# Power_supply.net
KiCad netlist of a schematic drawn in EAGLE
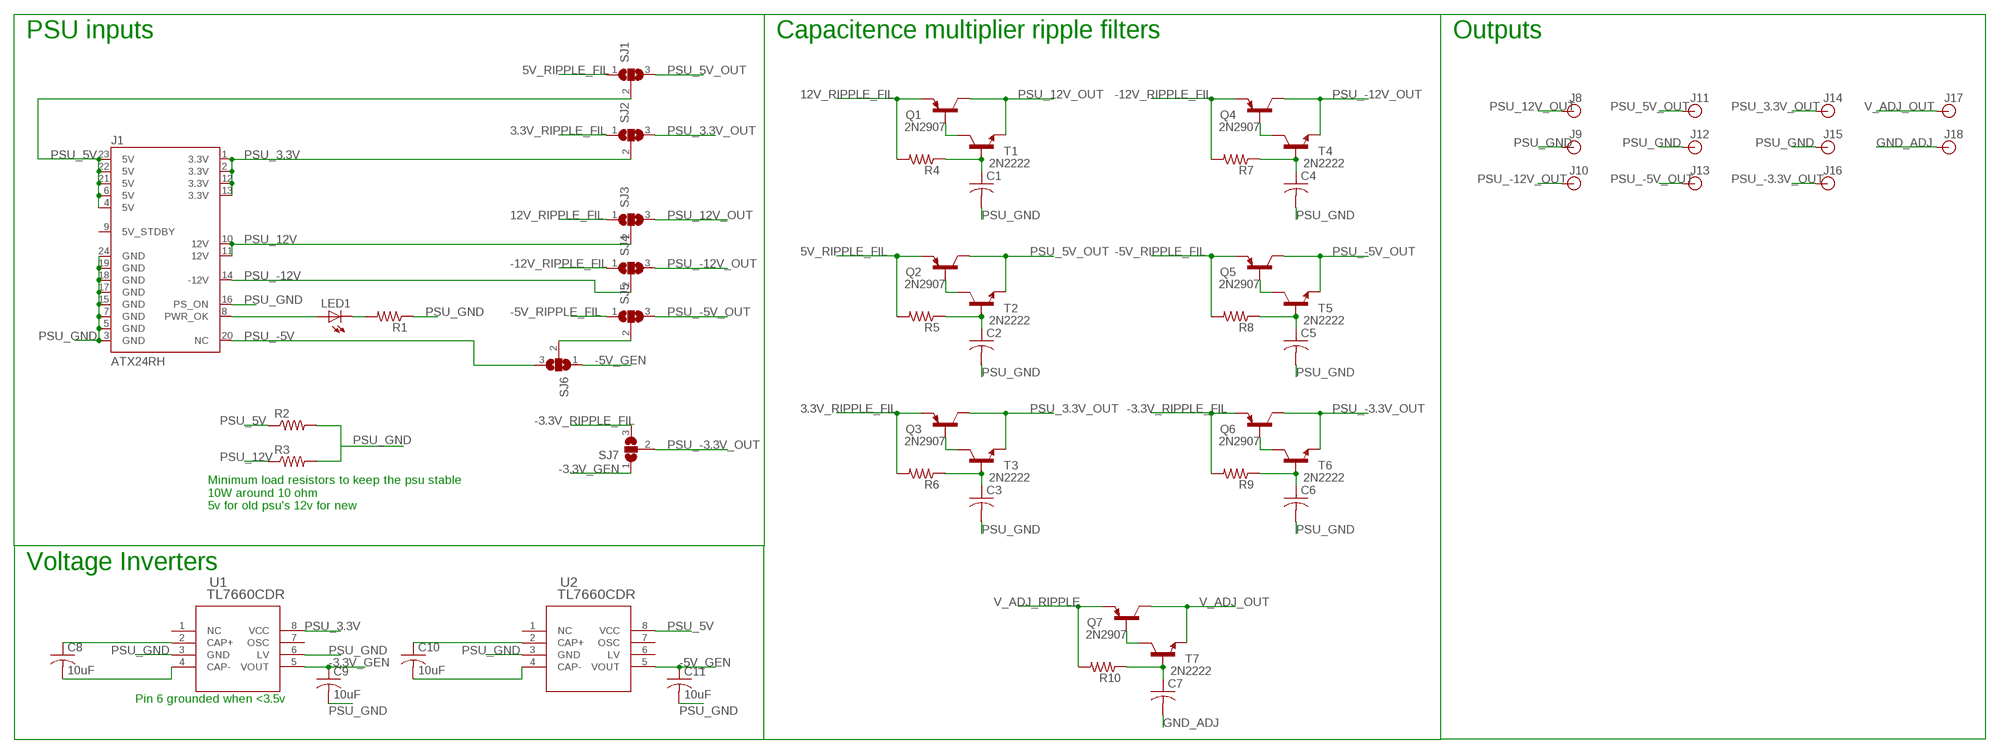
[diagram p0: schematic, sheet 1]
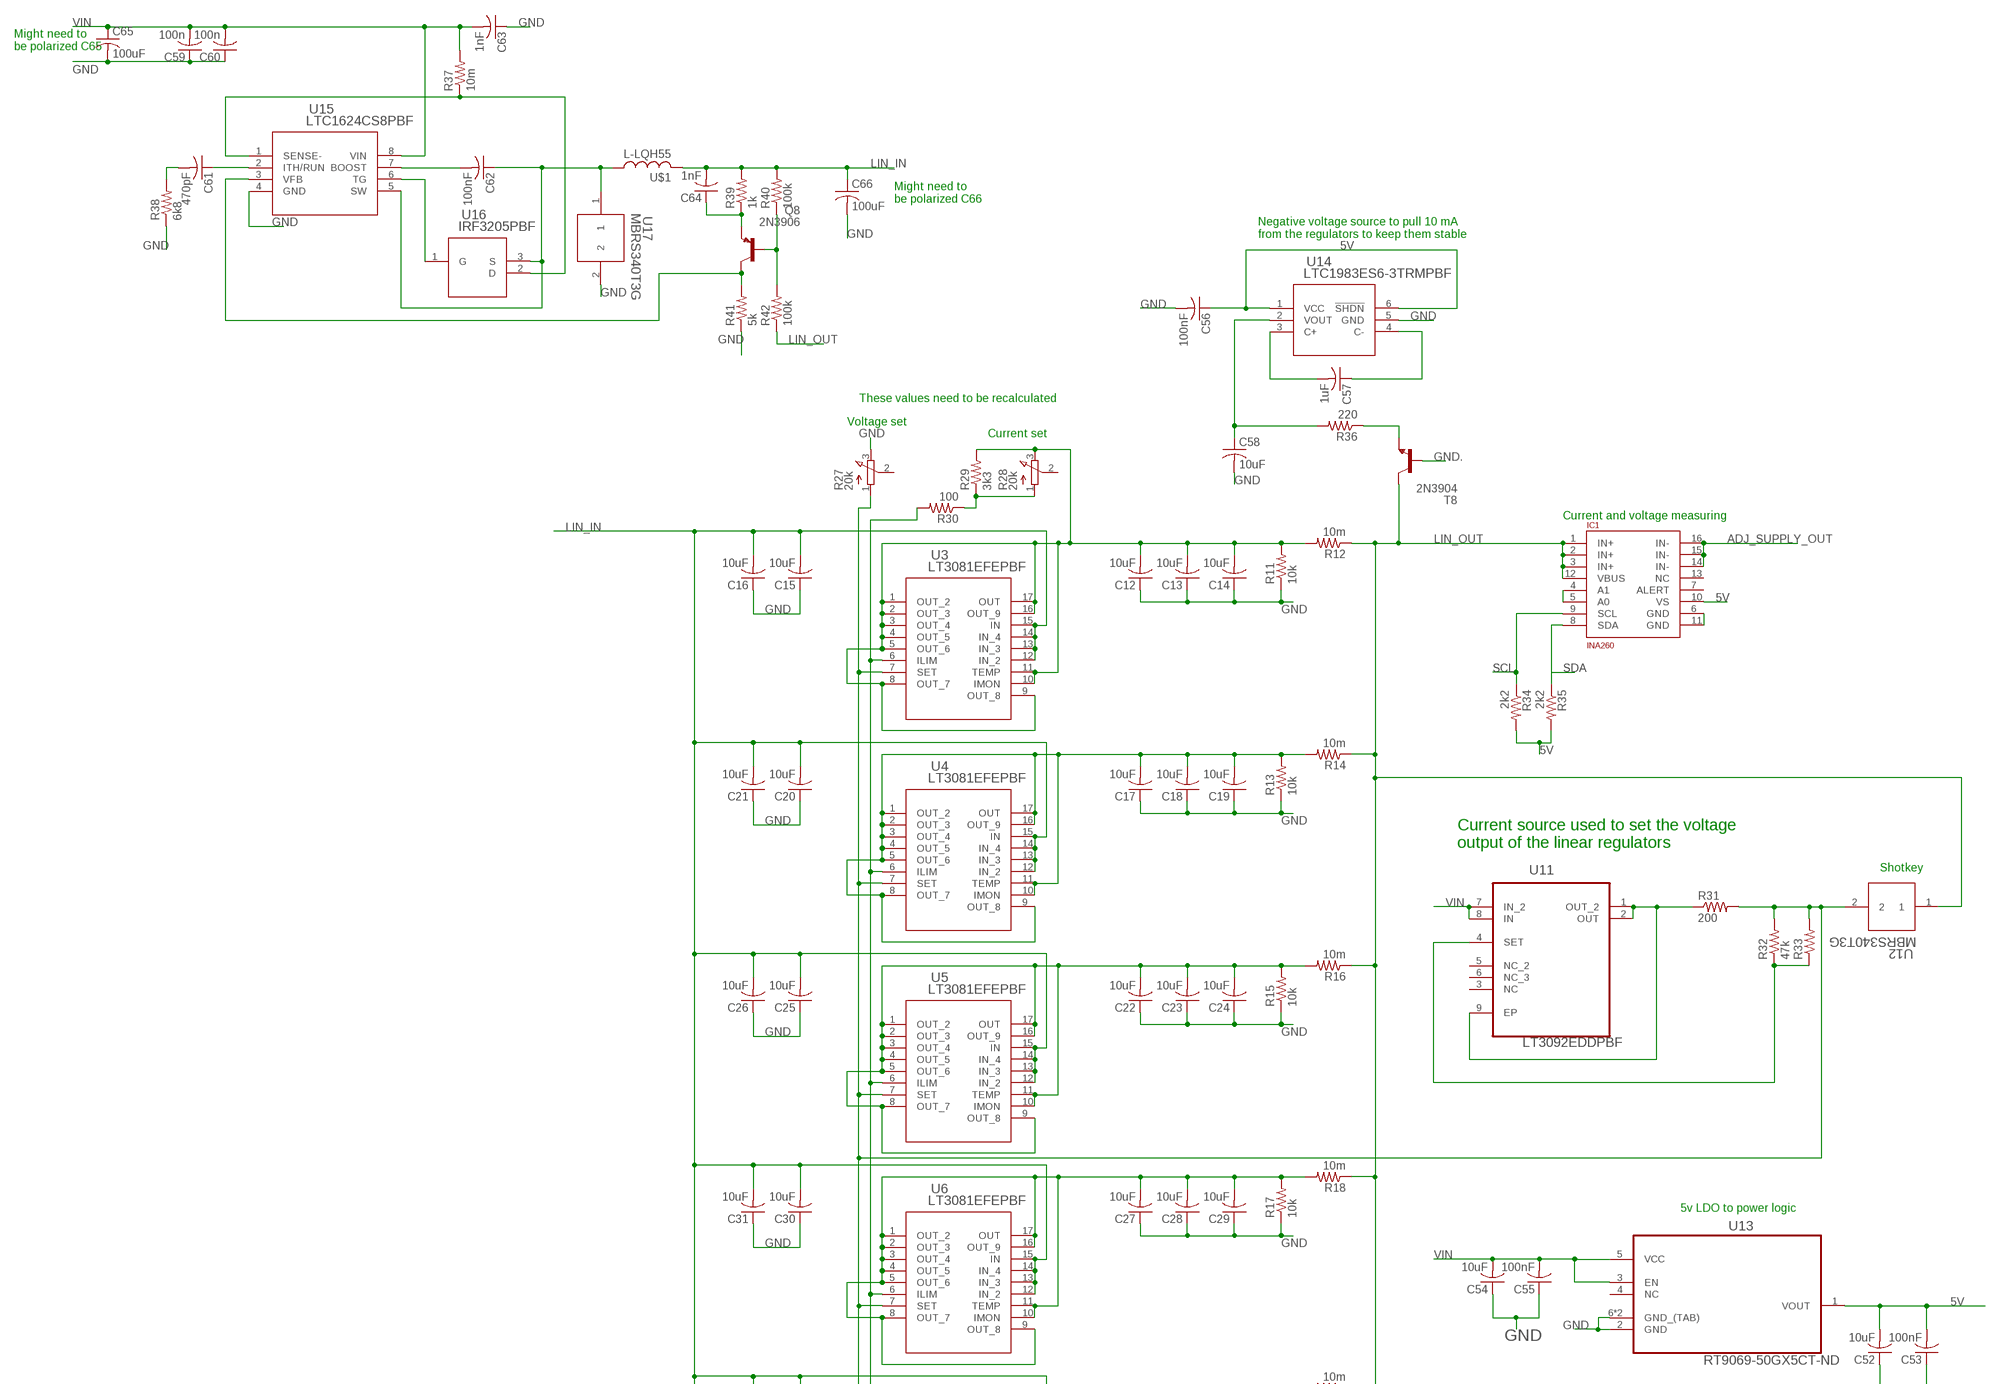
[diagram p1: schematic, sheet 2, part 1 of 2]
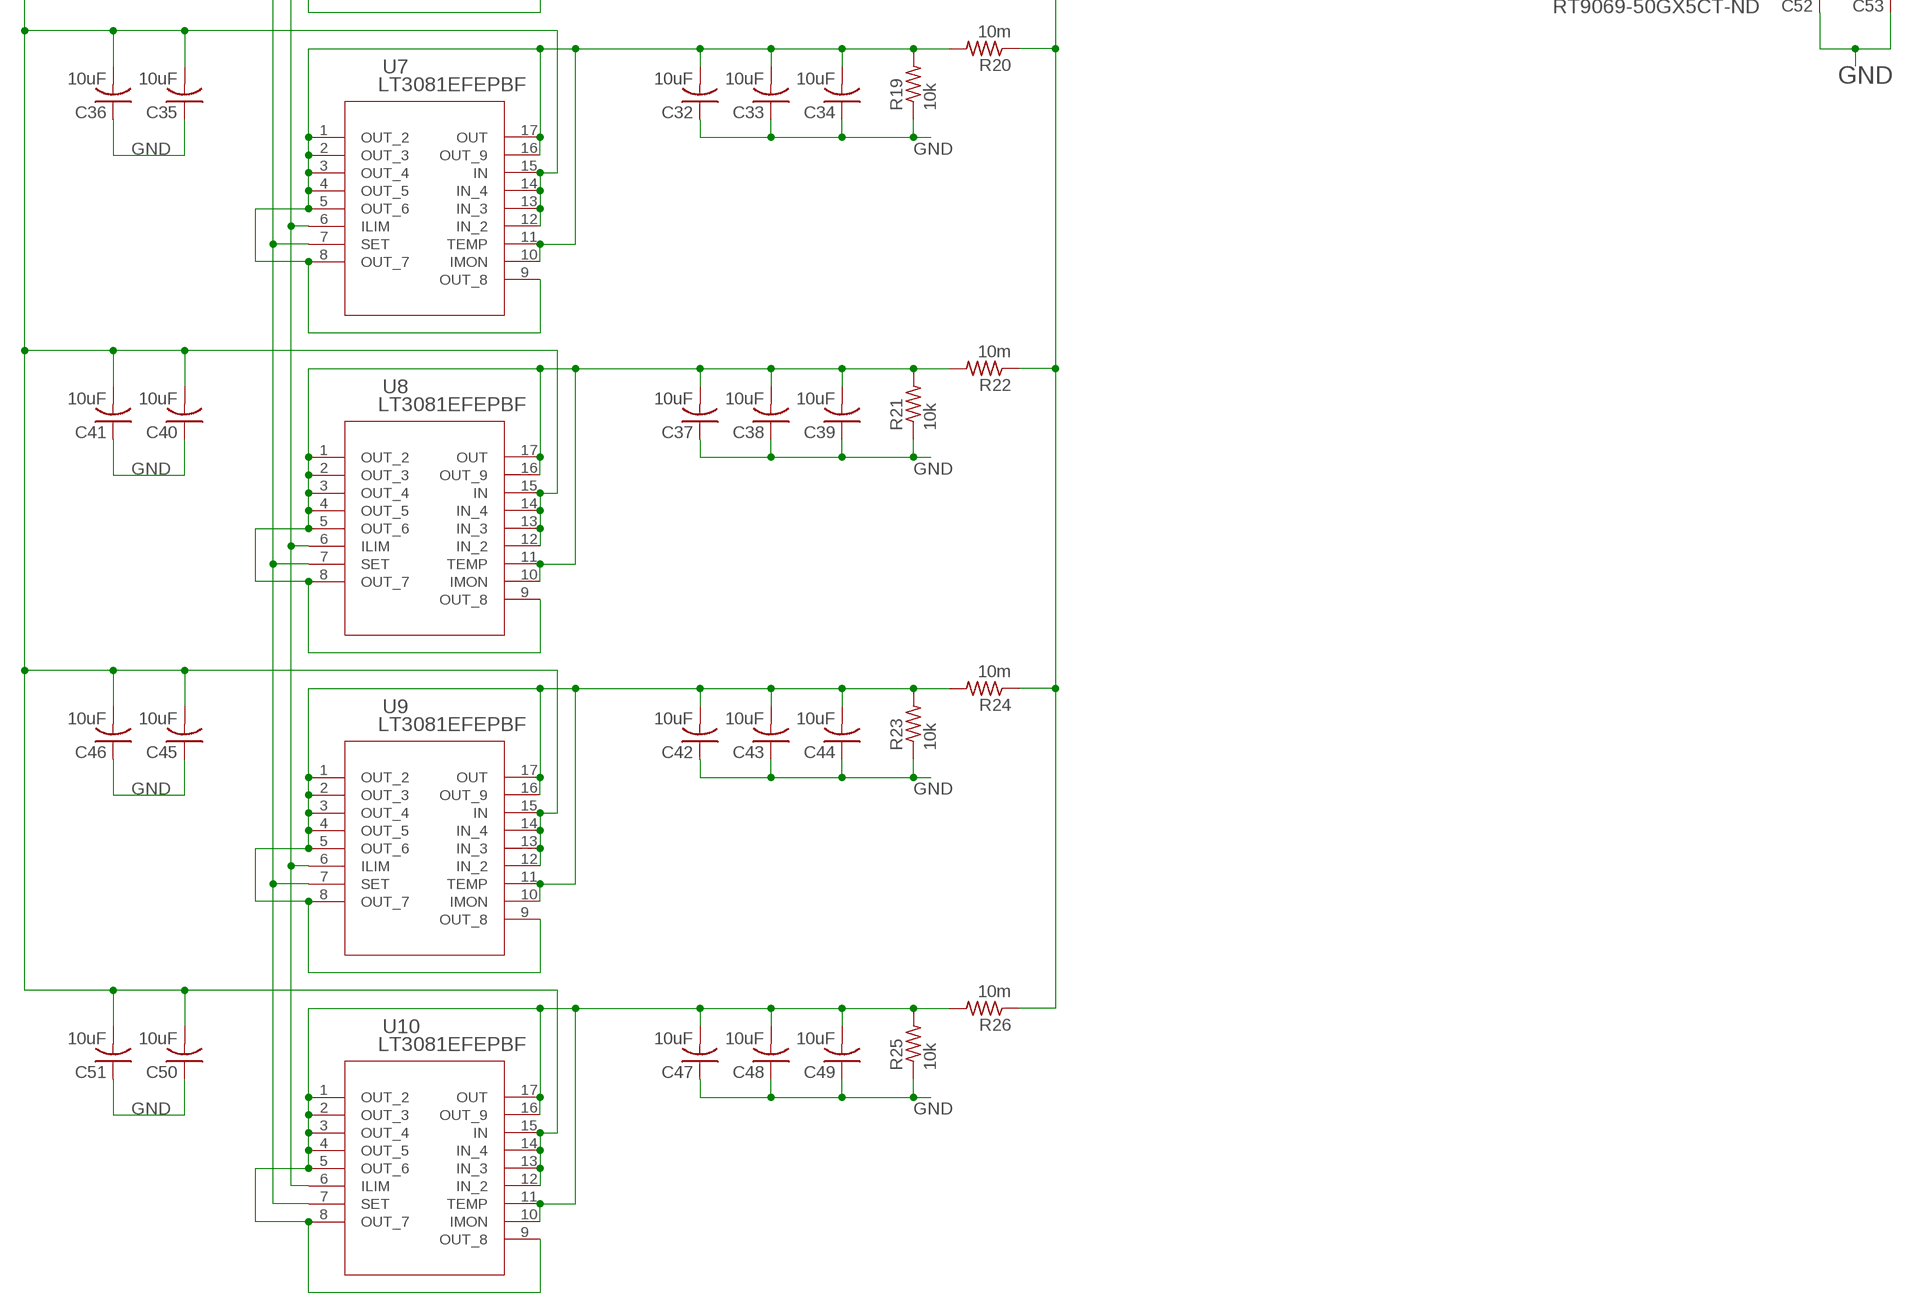
[diagram p2: schematic, sheet 2, part 2 of 2]

(export (version "E")
  (design (tool "Eeschema 10.0.6"))
  (components
    (comp (ref "C12")
      (value "10uF")
      (footprint "eagle-import:C0805")
      (libsource (lib "eagle-import") (part "C-USC0805"))
    )
    (comp (ref "C13")
      (value "10uF")
      (footprint "eagle-import:C0805")
      (libsource (lib "eagle-import") (part "C-USC0805"))
    )
    (comp (ref "C14")
      (value "10uF")
      (footprint "eagle-import:C0805")
      (libsource (lib "eagle-import") (part "C-USC0805"))
    )
    (comp (ref "C15")
      (value "10uF")
      (footprint "eagle-import:C0805")
      (libsource (lib "eagle-import") (part "C-USC0805"))
    )
    (comp (ref "C16")
      (value "10uF")
      (footprint "eagle-import:C0805")
      (libsource (lib "eagle-import") (part "C-USC0805"))
    )
    (comp (ref "C17")
      (value "10uF")
      (footprint "eagle-import:C0805")
      (libsource (lib "eagle-import") (part "C-USC0805"))
    )
    (comp (ref "C18")
      (value "10uF")
      (footprint "eagle-import:C0805")
      (libsource (lib "eagle-import") (part "C-USC0805"))
    )
    (comp (ref "C19")
      (value "10uF")
      (footprint "eagle-import:C0805")
      (libsource (lib "eagle-import") (part "C-USC0805"))
    )
    (comp (ref "C20")
      (value "10uF")
      (footprint "eagle-import:C0805")
      (libsource (lib "eagle-import") (part "C-USC0805"))
    )
    (comp (ref "C21")
      (value "10uF")
      (footprint "eagle-import:C0805")
      (libsource (lib "eagle-import") (part "C-USC0805"))
    )
    (comp (ref "C22")
      (value "10uF")
      (footprint "eagle-import:C0805")
      (libsource (lib "eagle-import") (part "C-USC0805"))
    )
    (comp (ref "C23")
      (value "10uF")
      (footprint "eagle-import:C0805")
      (libsource (lib "eagle-import") (part "C-USC0805"))
    )
    (comp (ref "C24")
      (value "10uF")
      (footprint "eagle-import:C0805")
      (libsource (lib "eagle-import") (part "C-USC0805"))
    )
    (comp (ref "C25")
      (value "10uF")
      (footprint "eagle-import:C0805")
      (libsource (lib "eagle-import") (part "C-USC0805"))
    )
    (comp (ref "C26")
      (value "10uF")
      (footprint "eagle-import:C0805")
      (libsource (lib "eagle-import") (part "C-USC0805"))
    )
    (comp (ref "C27")
      (value "10uF")
      (footprint "eagle-import:C0805")
      (libsource (lib "eagle-import") (part "C-USC0805"))
    )
    (comp (ref "C28")
      (value "10uF")
      (footprint "eagle-import:C0805")
      (libsource (lib "eagle-import") (part "C-USC0805"))
    )
    (comp (ref "C29")
      (value "10uF")
      (footprint "eagle-import:C0805")
      (libsource (lib "eagle-import") (part "C-USC0805"))
    )
    (comp (ref "C30")
      (value "10uF")
      (footprint "eagle-import:C0805")
      (libsource (lib "eagle-import") (part "C-USC0805"))
    )
    (comp (ref "C31")
      (value "10uF")
      (footprint "eagle-import:C0805")
      (libsource (lib "eagle-import") (part "C-USC0805"))
    )
    (comp (ref "C32")
      (value "10uF")
      (footprint "eagle-import:C0805")
      (libsource (lib "eagle-import") (part "C-USC0805"))
    )
    (comp (ref "C33")
      (value "10uF")
      (footprint "eagle-import:C0805")
      (libsource (lib "eagle-import") (part "C-USC0805"))
    )
    (comp (ref "C34")
      (value "10uF")
      (footprint "eagle-import:C0805")
      (libsource (lib "eagle-import") (part "C-USC0805"))
    )
    (comp (ref "C35")
      (value "10uF")
      (footprint "eagle-import:C0805")
      (libsource (lib "eagle-import") (part "C-USC0805"))
    )
    (comp (ref "C36")
      (value "10uF")
      (footprint "eagle-import:C0805")
      (libsource (lib "eagle-import") (part "C-USC0805"))
    )
    (comp (ref "C37")
      (value "10uF")
      (footprint "eagle-import:C0805")
      (libsource (lib "eagle-import") (part "C-USC0805"))
    )
    (comp (ref "C38")
      (value "10uF")
      (footprint "eagle-import:C0805")
      (libsource (lib "eagle-import") (part "C-USC0805"))
    )
    (comp (ref "C39")
      (value "10uF")
      (footprint "eagle-import:C0805")
      (libsource (lib "eagle-import") (part "C-USC0805"))
    )
    (comp (ref "C40")
      (value "10uF")
      (footprint "eagle-import:C0805")
      (libsource (lib "eagle-import") (part "C-USC0805"))
    )
    (comp (ref "C41")
      (value "10uF")
      (footprint "eagle-import:C0805")
      (libsource (lib "eagle-import") (part "C-USC0805"))
    )
    (comp (ref "C42")
      (value "10uF")
      (footprint "eagle-import:C0805")
      (libsource (lib "eagle-import") (part "C-USC0805"))
    )
    (comp (ref "C43")
      (value "10uF")
      (footprint "eagle-import:C0805")
      (libsource (lib "eagle-import") (part "C-USC0805"))
    )
    (comp (ref "C44")
      (value "10uF")
      (footprint "eagle-import:C0805")
      (libsource (lib "eagle-import") (part "C-USC0805"))
    )
    (comp (ref "C45")
      (value "10uF")
      (footprint "eagle-import:C0805")
      (libsource (lib "eagle-import") (part "C-USC0805"))
    )
    (comp (ref "C46")
      (value "10uF")
      (footprint "eagle-import:C0805")
      (libsource (lib "eagle-import") (part "C-USC0805"))
    )
    (comp (ref "C47")
      (value "10uF")
      (footprint "eagle-import:C0805")
      (libsource (lib "eagle-import") (part "C-USC0805"))
    )
    (comp (ref "C48")
      (value "10uF")
      (footprint "eagle-import:C0805")
      (libsource (lib "eagle-import") (part "C-USC0805"))
    )
    (comp (ref "C49")
      (value "10uF")
      (footprint "eagle-import:C0805")
      (libsource (lib "eagle-import") (part "C-USC0805"))
    )
    (comp (ref "C50")
      (value "10uF")
      (footprint "eagle-import:C0805")
      (libsource (lib "eagle-import") (part "C-USC0805"))
    )
    (comp (ref "C51")
      (value "10uF")
      (footprint "eagle-import:C0805")
      (libsource (lib "eagle-import") (part "C-USC0805"))
    )
    (comp (ref "C52")
      (value "10uF")
      (footprint "eagle-import:C0805")
      (libsource (lib "eagle-import") (part "C-USC0805"))
    )
    (comp (ref "C53")
      (value "100nF")
      (footprint "eagle-import:C0805")
      (libsource (lib "eagle-import") (part "C-USC0805"))
    )
    (comp (ref "C54")
      (value "10uF")
      (footprint "eagle-import:C0805")
      (libsource (lib "eagle-import") (part "C-USC0805"))
    )
    (comp (ref "C55")
      (value "100nF")
      (footprint "eagle-import:C0805")
      (libsource (lib "eagle-import") (part "C-USC0805"))
    )
    (comp (ref "C56")
      (value "100nF")
      (footprint "eagle-import:C0805")
      (libsource (lib "eagle-import") (part "C-USC0805"))
    )
    (comp (ref "C57")
      (value "1uF")
      (footprint "eagle-import:C0805")
      (libsource (lib "eagle-import") (part "C-USC0805"))
    )
    (comp (ref "C58")
      (value "10uF")
      (footprint "eagle-import:C0805")
      (libsource (lib "eagle-import") (part "C-USC0805"))
    )
    (comp (ref "C59")
      (value "100n")
      (footprint "eagle-import:C0805")
      (libsource (lib "eagle-import") (part "C-USC0805"))
    )
    (comp (ref "C60")
      (value "100n")
      (footprint "eagle-import:C0805")
      (libsource (lib "eagle-import") (part "C-USC0805"))
    )
    (comp (ref "C61")
      (value "470pF")
      (footprint "eagle-import:C0805")
      (libsource (lib "eagle-import") (part "C-USC0805"))
    )
    (comp (ref "C62")
      (value "100nF")
      (footprint "eagle-import:C0805")
      (libsource (lib "eagle-import") (part "C-USC0805"))
    )
    (comp (ref "C63")
      (value "1nF")
      (footprint "eagle-import:C0805")
      (libsource (lib "eagle-import") (part "C-USC0805"))
    )
    (comp (ref "C64")
      (value "1nF")
      (footprint "eagle-import:C0805")
      (libsource (lib "eagle-import") (part "C-USC0805"))
    )
    (comp (ref "C65")
      (value "100uF")
      (footprint "eagle-import:C0805")
      (libsource (lib "eagle-import") (part "C-USC0805"))
    )
    (comp (ref "C66")
      (value "100uF")
      (footprint "eagle-import:C0805")
      (libsource (lib "eagle-import") (part "C-USC0805"))
    )
    (comp (ref "IC1")
      (value "INA260")
      (footprint "eagle-import:TSSOP16")
      (libsource (lib "eagle-import") (part "INA260"))
    )
    (comp (ref "Q8")
      (value "2N3906")
      (footprint "eagle-import:TO92")
      (libsource (lib "eagle-import") (part "2N3906"))
    )
    (comp (ref "R11")
      (value "10k")
      (footprint "eagle-import:R0805")
      (libsource (lib "eagle-import") (part "R-US_R0805"))
    )
    (comp (ref "R12")
      (value "10m")
      (footprint "eagle-import:R0805")
      (libsource (lib "eagle-import") (part "R-US_R0805"))
    )
    (comp (ref "R13")
      (value "10k")
      (footprint "eagle-import:R0805")
      (libsource (lib "eagle-import") (part "R-US_R0805"))
    )
    (comp (ref "R14")
      (value "10m")
      (footprint "eagle-import:R0805")
      (libsource (lib "eagle-import") (part "R-US_R0805"))
    )
    (comp (ref "R15")
      (value "10k")
      (footprint "eagle-import:R0805")
      (libsource (lib "eagle-import") (part "R-US_R0805"))
    )
    (comp (ref "R16")
      (value "10m")
      (footprint "eagle-import:R0805")
      (libsource (lib "eagle-import") (part "R-US_R0805"))
    )
    (comp (ref "R17")
      (value "10k")
      (footprint "eagle-import:R0805")
      (libsource (lib "eagle-import") (part "R-US_R0805"))
    )
    (comp (ref "R18")
      (value "10m")
      (footprint "eagle-import:R0805")
      (libsource (lib "eagle-import") (part "R-US_R0805"))
    )
    (comp (ref "R19")
      (value "10k")
      (footprint "eagle-import:R0805")
      (libsource (lib "eagle-import") (part "R-US_R0805"))
    )
    (comp (ref "R20")
      (value "10m")
      (footprint "eagle-import:R0805")
      (libsource (lib "eagle-import") (part "R-US_R0805"))
    )
    (comp (ref "R21")
      (value "10k")
      (footprint "eagle-import:R0805")
      (libsource (lib "eagle-import") (part "R-US_R0805"))
    )
    (comp (ref "R22")
      (value "10m")
      (footprint "eagle-import:R0805")
      (libsource (lib "eagle-import") (part "R-US_R0805"))
    )
    (comp (ref "R23")
      (value "10k")
      (footprint "eagle-import:R0805")
      (libsource (lib "eagle-import") (part "R-US_R0805"))
    )
    (comp (ref "R24")
      (value "10m")
      (footprint "eagle-import:R0805")
      (libsource (lib "eagle-import") (part "R-US_R0805"))
    )
    (comp (ref "R25")
      (value "10k")
      (footprint "eagle-import:R0805")
      (libsource (lib "eagle-import") (part "R-US_R0805"))
    )
    (comp (ref "R26")
      (value "10m")
      (footprint "eagle-import:R0805")
      (libsource (lib "eagle-import") (part "R-US_R0805"))
    )
    (comp (ref "R27")
      (value "20k")
      (footprint "eagle-import:3RP_1610N")
      (libsource (lib "eagle-import") (part "3RP/1610N"))
    )
    (comp (ref "R28")
      (value "20k")
      (footprint "eagle-import:3RP_1610N")
      (libsource (lib "eagle-import") (part "3RP/1610N"))
    )
    (comp (ref "R29")
      (value "3k3")
      (footprint "eagle-import:R0603")
      (libsource (lib "eagle-import") (part "R-US_R0603"))
    )
    (comp (ref "R30")
      (value "100")
      (footprint "eagle-import:R0603")
      (libsource (lib "eagle-import") (part "R-US_R0603"))
    )
    (comp (ref "R31")
      (value "200")
      (footprint "eagle-import:R0603")
      (libsource (lib "eagle-import") (part "R-US_R0603"))
    )
    (comp (ref "R32")
      (value "47k")
      (footprint "eagle-import:R0603")
      (libsource (lib "eagle-import") (part "R-US_R0603"))
    )
    (comp (ref "R33")
      (value "R-US_R0603")
      (footprint "eagle-import:R0603")
      (libsource (lib "eagle-import") (part "R-US_R0603"))
    )
    (comp (ref "R34")
      (value "2k2")
      (footprint "eagle-import:R0805")
      (libsource (lib "eagle-import") (part "R-US_R0805"))
    )
    (comp (ref "R35")
      (value "2k2")
      (footprint "eagle-import:R0805")
      (libsource (lib "eagle-import") (part "R-US_R0805"))
    )
    (comp (ref "R36")
      (value "220")
      (footprint "eagle-import:R0805")
      (libsource (lib "eagle-import") (part "R-US_R0805"))
    )
    (comp (ref "R37")
      (value "10m")
      (footprint "eagle-import:R0603")
      (libsource (lib "eagle-import") (part "R-US_R0603"))
    )
    (comp (ref "R38")
      (value "6k8")
      (footprint "eagle-import:R0603")
      (libsource (lib "eagle-import") (part "R-US_R0603"))
    )
    (comp (ref "R39")
      (value "1k")
      (footprint "eagle-import:R0603")
      (libsource (lib "eagle-import") (part "R-US_R0603"))
    )
    (comp (ref "R40")
      (value "100k")
      (footprint "eagle-import:R0603")
      (libsource (lib "eagle-import") (part "R-US_R0603"))
    )
    (comp (ref "R41")
      (value "5k")
      (footprint "eagle-import:R0603")
      (libsource (lib "eagle-import") (part "R-US_R0603"))
    )
    (comp (ref "R42")
      (value "100k")
      (footprint "eagle-import:R0603")
      (libsource (lib "eagle-import") (part "R-US_R0603"))
    )
    (comp (ref "T8")
      (value "2N3904")
      (footprint "eagle-import:TO92")
      (libsource (lib "eagle-import") (part "2N3904"))
    )
    (comp (ref "U$1")
      (value "L-LQH55")
      (footprint "eagle-import:LQH55")
      (libsource (lib "eagle-import") (part "L-LQH55"))
    )
    (comp (ref "U3")
      (value "LT3081EFEPBF")
      (footprint "eagle-import:TSSOP-16_FE_BB")
      (fields (field (name "MANUFACTURER_PART_NUMBER") "LT3081EFE#PBF"))
      (libsource (lib "eagle-import") (part "LT3081EFEPBF"))
    )
    (comp (ref "U4")
      (value "LT3081EFEPBF")
      (footprint "eagle-import:TSSOP-16_FE_BB")
      (fields (field (name "MANUFACTURER_PART_NUMBER") "LT3081EFE#PBF"))
      (libsource (lib "eagle-import") (part "LT3081EFEPBF"))
    )
    (comp (ref "U5")
      (value "LT3081EFEPBF")
      (footprint "eagle-import:TSSOP-16_FE_BB")
      (fields (field (name "MANUFACTURER_PART_NUMBER") "LT3081EFE#PBF"))
      (libsource (lib "eagle-import") (part "LT3081EFEPBF"))
    )
    (comp (ref "U6")
      (value "LT3081EFEPBF")
      (footprint "eagle-import:TSSOP-16_FE_BB")
      (fields (field (name "MANUFACTURER_PART_NUMBER") "LT3081EFE#PBF"))
      (libsource (lib "eagle-import") (part "LT3081EFEPBF"))
    )
    (comp (ref "U7")
      (value "LT3081EFEPBF")
      (footprint "eagle-import:TSSOP-16_FE_BB")
      (fields (field (name "MANUFACTURER_PART_NUMBER") "LT3081EFE#PBF"))
      (libsource (lib "eagle-import") (part "LT3081EFEPBF"))
    )
    (comp (ref "U8")
      (value "LT3081EFEPBF")
      (footprint "eagle-import:TSSOP-16_FE_BB")
      (fields (field (name "MANUFACTURER_PART_NUMBER") "LT3081EFE#PBF"))
      (libsource (lib "eagle-import") (part "LT3081EFEPBF"))
    )
    (comp (ref "U9")
      (value "LT3081EFEPBF")
      (footprint "eagle-import:TSSOP-16_FE_BB")
      (fields (field (name "MANUFACTURER_PART_NUMBER") "LT3081EFE#PBF"))
      (libsource (lib "eagle-import") (part "LT3081EFEPBF"))
    )
    (comp (ref "U10")
      (value "LT3081EFEPBF")
      (footprint "eagle-import:TSSOP-16_FE_BB")
      (fields (field (name "MANUFACTURER_PART_NUMBER") "LT3081EFE#PBF"))
      (libsource (lib "eagle-import") (part "LT3081EFEPBF"))
    )
    (comp (ref "U11")
      (value "LT3092EDDPBF")
      (footprint "eagle-import:DFN300X300X80-9N")
      (fields (field (name "MPN") "LT3092EDD#PBF"))
      (libsource (lib "eagle-import") (part "LT3092EDDPBF"))
    )
    (comp (ref "U12")
      (value "MBRS340T3G")
      (footprint "eagle-import:SMC")
      (libsource (lib "eagle-import") (part "MBRS340T3G"))
    )
    (comp (ref "U13")
      (value "RT9069-50GX5CT-ND")
      (footprint "eagle-import:RT9069-50GX5CT-ND")
      (fields (field (name "MF") "Microchip") (field (name "MP") "MCP1826T-3002E/DC"))
      (libsource (lib "eagle-import") (part "RT9069-50GX5CT-ND"))
    )
    (comp (ref "U14")
      (value "LTC1983ES6-3TRMPBF")
      (footprint "eagle-import:SOT-23_S6")
      (fields (field (name "MANUFACTURER_PART_NUMBER") "LTC1983ES63#TRMPBF"))
      (libsource (lib "eagle-import") (part "LTC1983ES6-3TRMPBF"))
    )
    (comp (ref "U15")
      (value "LTC1624CS8PBF")
      (footprint "eagle-import:SO-8_S")
      (fields (field (name "MANUFACTURER_PART_NUMBER") "LTC1624CS8#PBF"))
      (libsource (lib "eagle-import") (part "LTC1624CS8PBF"))
    )
    (comp (ref "U16")
      (value "IRF3205PBF")
      (footprint "eagle-import:TO-220AB")
      (libsource (lib "eagle-import") (part "IRF3205PBF"))
    )
    (comp (ref "U17")
      (value "MBRS340T3G")
      (footprint "eagle-import:SMC")
      (libsource (lib "eagle-import") (part "MBRS340T3G"))
    )
    (comp (ref "C1")
      (value "C-USC0603")
      (footprint "eagle-import:C0603")
      (libsource (lib "eagle-import") (part "C-USC0603"))
    )
    (comp (ref "C2")
      (value "C-USC0603")
      (footprint "eagle-import:C0603")
      (libsource (lib "eagle-import") (part "C-USC0603"))
    )
    (comp (ref "C3")
      (value "C-USC0603")
      (footprint "eagle-import:C0603")
      (libsource (lib "eagle-import") (part "C-USC0603"))
    )
    (comp (ref "C4")
      (value "C-USC0603")
      (footprint "eagle-import:C0603")
      (libsource (lib "eagle-import") (part "C-USC0603"))
    )
    (comp (ref "C5")
      (value "C-USC0603")
      (footprint "eagle-import:C0603")
      (libsource (lib "eagle-import") (part "C-USC0603"))
    )
    (comp (ref "C6")
      (value "C-USC0603")
      (footprint "eagle-import:C0603")
      (libsource (lib "eagle-import") (part "C-USC0603"))
    )
    (comp (ref "C7")
      (value "C-USC0603")
      (footprint "eagle-import:C0603")
      (libsource (lib "eagle-import") (part "C-USC0603"))
    )
    (comp (ref "C8")
      (value "10uF")
      (footprint "eagle-import:C0603")
      (libsource (lib "eagle-import") (part "C-USC0603"))
    )
    (comp (ref "C9")
      (value "10uF")
      (footprint "eagle-import:C0603")
      (libsource (lib "eagle-import") (part "C-USC0603"))
    )
    (comp (ref "C10")
      (value "10uF")
      (footprint "eagle-import:C0603")
      (libsource (lib "eagle-import") (part "C-USC0603"))
    )
    (comp (ref "C11")
      (value "10uF")
      (footprint "eagle-import:C0603")
      (libsource (lib "eagle-import") (part "C-USC0603"))
    )
    (comp (ref "J1")
      (value "ATX24RH")
      (footprint "eagle-import:ATX24_RIGHT_ANGLE")
      (libsource (lib "eagle-import") (part "ATX24RH"))
    )
    (comp (ref "J8")
      (value "BANANA_CONN")
      (footprint "eagle-import:BANANA_CONN")
      (libsource (lib "eagle-import") (part "BANANA_CONN"))
    )
    (comp (ref "J9")
      (value "BANANA_CONN")
      (footprint "eagle-import:BANANA_CONN")
      (libsource (lib "eagle-import") (part "BANANA_CONN"))
    )
    (comp (ref "J10")
      (value "BANANA_CONN")
      (footprint "eagle-import:BANANA_CONN")
      (libsource (lib "eagle-import") (part "BANANA_CONN"))
    )
    (comp (ref "J11")
      (value "BANANA_CONN")
      (footprint "eagle-import:BANANA_CONN")
      (libsource (lib "eagle-import") (part "BANANA_CONN"))
    )
    (comp (ref "J12")
      (value "BANANA_CONN")
      (footprint "eagle-import:BANANA_CONN")
      (libsource (lib "eagle-import") (part "BANANA_CONN"))
    )
    (comp (ref "J13")
      (value "BANANA_CONN")
      (footprint "eagle-import:BANANA_CONN")
      (libsource (lib "eagle-import") (part "BANANA_CONN"))
    )
    (comp (ref "J14")
      (value "BANANA_CONN")
      (footprint "eagle-import:BANANA_CONN")
      (libsource (lib "eagle-import") (part "BANANA_CONN"))
    )
    (comp (ref "J15")
      (value "BANANA_CONN")
      (footprint "eagle-import:BANANA_CONN")
      (libsource (lib "eagle-import") (part "BANANA_CONN"))
    )
    (comp (ref "J16")
      (value "BANANA_CONN")
      (footprint "eagle-import:BANANA_CONN")
      (libsource (lib "eagle-import") (part "BANANA_CONN"))
    )
    (comp (ref "J17")
      (value "BANANA_CONN")
      (footprint "eagle-import:BANANA_CONN")
      (libsource (lib "eagle-import") (part "BANANA_CONN"))
    )
    (comp (ref "J18")
      (value "BANANA_CONN")
      (footprint "eagle-import:BANANA_CONN")
      (libsource (lib "eagle-import") (part "BANANA_CONN"))
    )
    (comp (ref "LED1")
      (value "LED3MM")
      (footprint "eagle-import:LED3MM")
      (libsource (lib "eagle-import") (part "LED3MM"))
    )
    (comp (ref "Q1")
      (value "2N2907")
      (footprint "eagle-import:TO92-EBC-OVAL")
      (libsource (lib "eagle-import") (part "2N2907"))
    )
    (comp (ref "Q2")
      (value "2N2907")
      (footprint "eagle-import:TO92-EBC-OVAL")
      (libsource (lib "eagle-import") (part "2N2907"))
    )
    (comp (ref "Q3")
      (value "2N2907")
      (footprint "eagle-import:TO92-EBC-OVAL")
      (libsource (lib "eagle-import") (part "2N2907"))
    )
    (comp (ref "Q4")
      (value "2N2907")
      (footprint "eagle-import:TO92-EBC-OVAL")
      (libsource (lib "eagle-import") (part "2N2907"))
    )
    (comp (ref "Q5")
      (value "2N2907")
      (footprint "eagle-import:TO92-EBC-OVAL")
      (libsource (lib "eagle-import") (part "2N2907"))
    )
    (comp (ref "Q6")
      (value "2N2907")
      (footprint "eagle-import:TO92-EBC-OVAL")
      (libsource (lib "eagle-import") (part "2N2907"))
    )
    (comp (ref "Q7")
      (value "2N2907")
      (footprint "eagle-import:TO92-EBC-OVAL")
      (libsource (lib "eagle-import") (part "2N2907"))
    )
    (comp (ref "R1")
      (value "R-US_R0603")
      (footprint "eagle-import:R0603")
      (libsource (lib "eagle-import") (part "R-US_R0603"))
    )
    (comp (ref "R2")
      (value "R-US_0613/15")
      (footprint "eagle-import:P0613_15")
      (libsource (lib "eagle-import") (part "R-US_0613/15"))
    )
    (comp (ref "R3")
      (value "R-US_0613/15")
      (footprint "eagle-import:P0613_15")
      (libsource (lib "eagle-import") (part "R-US_0613/15"))
    )
    (comp (ref "R4")
      (value "R-US_R0603")
      (footprint "eagle-import:R0603")
      (libsource (lib "eagle-import") (part "R-US_R0603"))
    )
    (comp (ref "R5")
      (value "R-US_R0603")
      (footprint "eagle-import:R0603")
      (libsource (lib "eagle-import") (part "R-US_R0603"))
    )
    (comp (ref "R6")
      (value "R-US_R0603")
      (footprint "eagle-import:R0603")
      (libsource (lib "eagle-import") (part "R-US_R0603"))
    )
    (comp (ref "R7")
      (value "R-US_R0603")
      (footprint "eagle-import:R0603")
      (libsource (lib "eagle-import") (part "R-US_R0603"))
    )
    (comp (ref "R8")
      (value "R-US_R0603")
      (footprint "eagle-import:R0603")
      (libsource (lib "eagle-import") (part "R-US_R0603"))
    )
    (comp (ref "R9")
      (value "R-US_R0603")
      (footprint "eagle-import:R0603")
      (libsource (lib "eagle-import") (part "R-US_R0603"))
    )
    (comp (ref "R10")
      (value "R-US_R0603")
      (footprint "eagle-import:R0603")
      (libsource (lib "eagle-import") (part "R-US_R0603"))
    )
    (comp (ref "SJ1")
      (value "SJ2WW")
      (footprint "eagle-import:SJ_2W")
      (libsource (lib "eagle-import") (part "SJ2WW"))
    )
    (comp (ref "SJ2")
      (value "SJ2WW")
      (footprint "eagle-import:SJ_2W")
      (libsource (lib "eagle-import") (part "SJ2WW"))
    )
    (comp (ref "SJ3")
      (value "SJ2WW")
      (footprint "eagle-import:SJ_2W")
      (libsource (lib "eagle-import") (part "SJ2WW"))
    )
    (comp (ref "SJ4")
      (value "SJ2WW")
      (footprint "eagle-import:SJ_2W")
      (libsource (lib "eagle-import") (part "SJ2WW"))
    )
    (comp (ref "SJ5")
      (value "SJ2WW")
      (footprint "eagle-import:SJ_2W")
      (libsource (lib "eagle-import") (part "SJ2WW"))
    )
    (comp (ref "SJ6")
      (value "SJ2WW")
      (footprint "eagle-import:SJ_2W")
      (libsource (lib "eagle-import") (part "SJ2WW"))
    )
    (comp (ref "SJ7")
      (value "SJ2WW")
      (footprint "eagle-import:SJ_2W")
      (libsource (lib "eagle-import") (part "SJ2WW"))
    )
    (comp (ref "T1")
      (value "2N2222")
      (footprint "eagle-import:TO92-EBC-OVAL")
      (libsource (lib "eagle-import") (part "2N2222"))
    )
    (comp (ref "T2")
      (value "2N2222")
      (footprint "eagle-import:TO92-EBC-OVAL")
      (libsource (lib "eagle-import") (part "2N2222"))
    )
    (comp (ref "T3")
      (value "2N2222")
      (footprint "eagle-import:TO92-EBC-OVAL")
      (libsource (lib "eagle-import") (part "2N2222"))
    )
    (comp (ref "T4")
      (value "2N2222")
      (footprint "eagle-import:TO92-EBC-OVAL")
      (libsource (lib "eagle-import") (part "2N2222"))
    )
    (comp (ref "T5")
      (value "2N2222")
      (footprint "eagle-import:TO92-EBC-OVAL")
      (libsource (lib "eagle-import") (part "2N2222"))
    )
    (comp (ref "T6")
      (value "2N2222")
      (footprint "eagle-import:TO92-EBC-OVAL")
      (libsource (lib "eagle-import") (part "2N2222"))
    )
    (comp (ref "T7")
      (value "2N2222")
      (footprint "eagle-import:TO92-EBC-OVAL")
      (libsource (lib "eagle-import") (part "2N2222"))
    )
    (comp (ref "U1")
      (value "TL7660CDR")
      (footprint "eagle-import:D8")
      (libsource (lib "eagle-import") (part "TL7660CDR"))
    )
    (comp (ref "U2")
      (value "TL7660CDR")
      (footprint "eagle-import:D8")
      (libsource (lib "eagle-import") (part "TL7660CDR"))
    )
  )
  (nets
    (net (code "1") (name "-3.3V_GEN") (class "Default")
      (node (ref "C9") (pin "1") (pinfunction "1_1") (pintype "passive"))
      (node (ref "SJ7") (pin "1") (pinfunction "1_1") (pintype "passive"))
      (node (ref "U1") (pin "5") (pinfunction "VOUT_5") (pintype "output"))
    )
    (net (code "2") (name "-3.3V_RIPPLE_FIL") (class "Default")
      (node (ref "Q6") (pin "E") (pinfunction "E_E") (pintype "passive"))
      (node (ref "R9") (pin "2") (pinfunction "2_2") (pintype "passive"))
      (node (ref "SJ7") (pin "3") (pinfunction "3_3") (pintype "passive"))
    )
    (net (code "3") (name "-5V_GEN") (class "Default")
      (node (ref "C11") (pin "1") (pinfunction "1_1") (pintype "passive"))
      (node (ref "SJ6") (pin "1") (pinfunction "1_1") (pintype "passive"))
      (node (ref "U2") (pin "5") (pinfunction "VOUT_5") (pintype "output"))
    )
    (net (code "4") (name "-5V_RIPPLE_FIL") (class "Default")
      (node (ref "Q5") (pin "E") (pinfunction "E_E") (pintype "passive"))
      (node (ref "R8") (pin "2") (pinfunction "2_2") (pintype "passive"))
      (node (ref "SJ5") (pin "1") (pinfunction "1_1") (pintype "passive"))
    )
    (net (code "5") (name "-12V_RIPPLE_FIL") (class "Default")
      (node (ref "Q4") (pin "E") (pinfunction "E_E") (pintype "passive"))
      (node (ref "R7") (pin "2") (pinfunction "2_2") (pintype "passive"))
      (node (ref "SJ4") (pin "1") (pinfunction "1_1") (pintype "passive"))
    )
    (net (code "6") (name "3.3V_RIPPLE_FIL") (class "Default")
      (node (ref "Q3") (pin "E") (pinfunction "E_E") (pintype "passive"))
      (node (ref "R6") (pin "2") (pinfunction "2_2") (pintype "passive"))
      (node (ref "SJ2") (pin "1") (pinfunction "1_1") (pintype "passive"))
    )
    (net (code "7") (name "5V") (class "Default")
      (node (ref "C52") (pin "2") (pinfunction "2_2") (pintype "passive"))
      (node (ref "C53") (pin "2") (pinfunction "2_2") (pintype "passive"))
      (node (ref "C56") (pin "1") (pinfunction "1_1") (pintype "passive"))
      (node (ref "IC1") (pin "10") (pinfunction "VS_10") (pintype "bidirectional"))
      (node (ref "R34") (pin "2") (pinfunction "2_2") (pintype "passive"))
      (node (ref "R35") (pin "2") (pinfunction "2_2") (pintype "passive"))
      (node (ref "U13") (pin "1") (pinfunction "VOUT_1") (pintype "output"))
      (node (ref "U14") (pin "1") (pinfunction "VCC_1") (pintype "power_in"))
      (node (ref "U14") (pin "6") (pinfunction "~{SHDN}_6") (pintype "passive"))
    )
    (net (code "8") (name "5V_RIPPLE_FIL") (class "Default")
      (node (ref "Q2") (pin "E") (pinfunction "E_E") (pintype "passive"))
      (node (ref "R5") (pin "2") (pinfunction "2_2") (pintype "passive"))
      (node (ref "SJ1") (pin "1") (pinfunction "1_1") (pintype "passive"))
    )
    (net (code "9") (name "12V_RIPPLE_FIL") (class "Default")
      (node (ref "Q1") (pin "E") (pinfunction "E_E") (pintype "passive"))
      (node (ref "R4") (pin "2") (pinfunction "2_2") (pintype "passive"))
      (node (ref "SJ3") (pin "1") (pinfunction "1_1") (pintype "passive"))
    )
    (net (code "10") (name "ADJ_SUPPLY_OUT") (class "Default")
      (node (ref "IC1") (pin "14") (pinfunction "IN-_14") (pintype "bidirectional"))
      (node (ref "IC1") (pin "15") (pinfunction "IN-_15") (pintype "bidirectional"))
      (node (ref "IC1") (pin "16") (pinfunction "IN-_16") (pintype "bidirectional"))
    )
    (net (code "11") (name "GND") (class "Default")
      (node (ref "C12") (pin "1") (pinfunction "1_1") (pintype "passive"))
      (node (ref "C13") (pin "1") (pinfunction "1_1") (pintype "passive"))
      (node (ref "C14") (pin "1") (pinfunction "1_1") (pintype "passive"))
      (node (ref "C15") (pin "1") (pinfunction "1_1") (pintype "passive"))
      (node (ref "C16") (pin "1") (pinfunction "1_1") (pintype "passive"))
      (node (ref "C17") (pin "1") (pinfunction "1_1") (pintype "passive"))
      (node (ref "C18") (pin "1") (pinfunction "1_1") (pintype "passive"))
      (node (ref "C19") (pin "1") (pinfunction "1_1") (pintype "passive"))
      (node (ref "C20") (pin "1") (pinfunction "1_1") (pintype "passive"))
      (node (ref "C21") (pin "1") (pinfunction "1_1") (pintype "passive"))
      (node (ref "C22") (pin "1") (pinfunction "1_1") (pintype "passive"))
      (node (ref "C23") (pin "1") (pinfunction "1_1") (pintype "passive"))
      (node (ref "C24") (pin "1") (pinfunction "1_1") (pintype "passive"))
      (node (ref "C25") (pin "1") (pinfunction "1_1") (pintype "passive"))
      (node (ref "C26") (pin "1") (pinfunction "1_1") (pintype "passive"))
      (node (ref "C27") (pin "1") (pinfunction "1_1") (pintype "passive"))
      (node (ref "C28") (pin "1") (pinfunction "1_1") (pintype "passive"))
      (node (ref "C29") (pin "1") (pinfunction "1_1") (pintype "passive"))
      (node (ref "C30") (pin "1") (pinfunction "1_1") (pintype "passive"))
      (node (ref "C31") (pin "1") (pinfunction "1_1") (pintype "passive"))
      (node (ref "C32") (pin "1") (pinfunction "1_1") (pintype "passive"))
      (node (ref "C33") (pin "1") (pinfunction "1_1") (pintype "passive"))
      (node (ref "C34") (pin "1") (pinfunction "1_1") (pintype "passive"))
      (node (ref "C35") (pin "1") (pinfunction "1_1") (pintype "passive"))
      (node (ref "C36") (pin "1") (pinfunction "1_1") (pintype "passive"))
      (node (ref "C37") (pin "1") (pinfunction "1_1") (pintype "passive"))
      (node (ref "C38") (pin "1") (pinfunction "1_1") (pintype "passive"))
      (node (ref "C39") (pin "1") (pinfunction "1_1") (pintype "passive"))
      (node (ref "C40") (pin "1") (pinfunction "1_1") (pintype "passive"))
      (node (ref "C41") (pin "1") (pinfunction "1_1") (pintype "passive"))
      (node (ref "C42") (pin "1") (pinfunction "1_1") (pintype "passive"))
      (node (ref "C43") (pin "1") (pinfunction "1_1") (pintype "passive"))
      (node (ref "C44") (pin "1") (pinfunction "1_1") (pintype "passive"))
      (node (ref "C45") (pin "1") (pinfunction "1_1") (pintype "passive"))
      (node (ref "C46") (pin "1") (pinfunction "1_1") (pintype "passive"))
      (node (ref "C47") (pin "1") (pinfunction "1_1") (pintype "passive"))
      (node (ref "C48") (pin "1") (pinfunction "1_1") (pintype "passive"))
      (node (ref "C49") (pin "1") (pinfunction "1_1") (pintype "passive"))
      (node (ref "C50") (pin "1") (pinfunction "1_1") (pintype "passive"))
      (node (ref "C51") (pin "1") (pinfunction "1_1") (pintype "passive"))
      (node (ref "C52") (pin "1") (pinfunction "1_1") (pintype "passive"))
      (node (ref "C53") (pin "1") (pinfunction "1_1") (pintype "passive"))
      (node (ref "C54") (pin "1") (pinfunction "1_1") (pintype "passive"))
      (node (ref "C55") (pin "1") (pinfunction "1_1") (pintype "passive"))
      (node (ref "C56") (pin "2") (pinfunction "2_2") (pintype "passive"))
      (node (ref "C58") (pin "2") (pinfunction "2_2") (pintype "passive"))
      (node (ref "C59") (pin "1") (pinfunction "1_1") (pintype "passive"))
      (node (ref "C60") (pin "1") (pinfunction "1_1") (pintype "passive"))
      (node (ref "C63") (pin "1") (pinfunction "1_1") (pintype "passive"))
      (node (ref "C65") (pin "2") (pinfunction "2_2") (pintype "passive"))
      (node (ref "C66") (pin "2") (pinfunction "2_2") (pintype "passive"))
      (node (ref "R11") (pin "1") (pinfunction "1_1") (pintype "passive"))
      (node (ref "R13") (pin "1") (pinfunction "1_1") (pintype "passive"))
      (node (ref "R15") (pin "1") (pinfunction "1_1") (pintype "passive"))
      (node (ref "R17") (pin "1") (pinfunction "1_1") (pintype "passive"))
      (node (ref "R19") (pin "1") (pinfunction "1_1") (pintype "passive"))
      (node (ref "R21") (pin "1") (pinfunction "1_1") (pintype "passive"))
      (node (ref "R23") (pin "1") (pinfunction "1_1") (pintype "passive"))
      (node (ref "R25") (pin "1") (pinfunction "1_1") (pintype "passive"))
      (node (ref "R27") (pin "3") (pinfunction "E_3") (pintype "passive"))
      (node (ref "R38") (pin "1") (pinfunction "1_1") (pintype "passive"))
      (node (ref "R41") (pin "1") (pinfunction "1_1") (pintype "passive"))
      (node (ref "U13") (pin "2") (pinfunction "GND_2") (pintype "passive"))
      (node (ref "U13") (pin "6") (pinfunction "GND_(TAB)_6") (pintype "passive"))
      (node (ref "U13") (pin "TAB") (pinfunction "GND_(TAB)_TAB") (pintype "passive"))
      (node (ref "U14") (pin "5") (pinfunction "GND_5") (pintype "power_in"))
      (node (ref "U15") (pin "4") (pinfunction "GND_4") (pintype "power_in"))
      (node (ref "U17") (pin "2") (pinfunction "2_2") (pintype "passive"))
    )
    (net (code "12") (name "GND.") (class "Default")
      (node (ref "T8") (pin "2") (pinfunction "B_2") (pintype "passive"))
    )
    (net (code "13") (name "GND_ADJ") (class "Default")
      (node (ref "C7") (pin "2") (pinfunction "2_2") (pintype "passive"))
      (node (ref "J18") (pin "P$1") (pinfunction "1_P$1") (pintype "passive"))
    )
    (net (code "14") (name "LIN_IN") (class "Default")
      (node (ref "C15") (pin "2") (pinfunction "2_2") (pintype "passive"))
      (node (ref "C16") (pin "2") (pinfunction "2_2") (pintype "passive"))
      (node (ref "C20") (pin "2") (pinfunction "2_2") (pintype "passive"))
      (node (ref "C21") (pin "2") (pinfunction "2_2") (pintype "passive"))
      (node (ref "C25") (pin "2") (pinfunction "2_2") (pintype "passive"))
      (node (ref "C26") (pin "2") (pinfunction "2_2") (pintype "passive"))
      (node (ref "C30") (pin "2") (pinfunction "2_2") (pintype "passive"))
      (node (ref "C31") (pin "2") (pinfunction "2_2") (pintype "passive"))
      (node (ref "C35") (pin "2") (pinfunction "2_2") (pintype "passive"))
      (node (ref "C36") (pin "2") (pinfunction "2_2") (pintype "passive"))
      (node (ref "C40") (pin "2") (pinfunction "2_2") (pintype "passive"))
      (node (ref "C41") (pin "2") (pinfunction "2_2") (pintype "passive"))
      (node (ref "C45") (pin "2") (pinfunction "2_2") (pintype "passive"))
      (node (ref "C46") (pin "2") (pinfunction "2_2") (pintype "passive"))
      (node (ref "C50") (pin "2") (pinfunction "2_2") (pintype "passive"))
      (node (ref "C51") (pin "2") (pinfunction "2_2") (pintype "passive"))
      (node (ref "C64") (pin "2") (pinfunction "2_2") (pintype "passive"))
      (node (ref "C66") (pin "1") (pinfunction "1_1") (pintype "passive"))
      (node (ref "R39") (pin "2") (pinfunction "2_2") (pintype "passive"))
      (node (ref "R40") (pin "2") (pinfunction "2_2") (pintype "passive"))
      (node (ref "U$1") (pin "2") (pinfunction "2_2") (pintype "passive"))
      (node (ref "U10") (pin "12") (pinfunction "IN_2_12") (pintype "input"))
      (node (ref "U10") (pin "13") (pinfunction "IN_3_13") (pintype "input"))
      (node (ref "U10") (pin "14") (pinfunction "IN_4_14") (pintype "input"))
      (node (ref "U10") (pin "15") (pinfunction "IN_15") (pintype "input"))
      (node (ref "U3") (pin "12") (pinfunction "IN_2_12") (pintype "input"))
      (node (ref "U3") (pin "13") (pinfunction "IN_3_13") (pintype "input"))
      (node (ref "U3") (pin "14") (pinfunction "IN_4_14") (pintype "input"))
      (node (ref "U3") (pin "15") (pinfunction "IN_15") (pintype "input"))
      (node (ref "U4") (pin "12") (pinfunction "IN_2_12") (pintype "input"))
      (node (ref "U4") (pin "13") (pinfunction "IN_3_13") (pintype "input"))
      (node (ref "U4") (pin "14") (pinfunction "IN_4_14") (pintype "input"))
      (node (ref "U4") (pin "15") (pinfunction "IN_15") (pintype "input"))
      (node (ref "U5") (pin "12") (pinfunction "IN_2_12") (pintype "input"))
      (node (ref "U5") (pin "13") (pinfunction "IN_3_13") (pintype "input"))
      (node (ref "U5") (pin "14") (pinfunction "IN_4_14") (pintype "input"))
      (node (ref "U5") (pin "15") (pinfunction "IN_15") (pintype "input"))
      (node (ref "U6") (pin "12") (pinfunction "IN_2_12") (pintype "input"))
      (node (ref "U6") (pin "13") (pinfunction "IN_3_13") (pintype "input"))
      (node (ref "U6") (pin "14") (pinfunction "IN_4_14") (pintype "input"))
      (node (ref "U6") (pin "15") (pinfunction "IN_15") (pintype "input"))
      (node (ref "U7") (pin "12") (pinfunction "IN_2_12") (pintype "input"))
      (node (ref "U7") (pin "13") (pinfunction "IN_3_13") (pintype "input"))
      (node (ref "U7") (pin "14") (pinfunction "IN_4_14") (pintype "input"))
      (node (ref "U7") (pin "15") (pinfunction "IN_15") (pintype "input"))
      (node (ref "U8") (pin "12") (pinfunction "IN_2_12") (pintype "input"))
      (node (ref "U8") (pin "13") (pinfunction "IN_3_13") (pintype "input"))
      (node (ref "U8") (pin "14") (pinfunction "IN_4_14") (pintype "input"))
      (node (ref "U8") (pin "15") (pinfunction "IN_15") (pintype "input"))
      (node (ref "U9") (pin "12") (pinfunction "IN_2_12") (pintype "input"))
      (node (ref "U9") (pin "13") (pinfunction "IN_3_13") (pintype "input"))
      (node (ref "U9") (pin "14") (pinfunction "IN_4_14") (pintype "input"))
      (node (ref "U9") (pin "15") (pinfunction "IN_15") (pintype "input"))
    )
    (net (code "15") (name "LIN_OUT") (class "Default")
      (node (ref "IC1") (pin "1") (pinfunction "IN+_1") (pintype "bidirectional"))
      (node (ref "IC1") (pin "12") (pinfunction "VBUS_12") (pintype "bidirectional"))
      (node (ref "IC1") (pin "2") (pinfunction "IN+_2") (pintype "bidirectional"))
      (node (ref "IC1") (pin "3") (pinfunction "IN+_3") (pintype "bidirectional"))
      (node (ref "R12") (pin "1") (pinfunction "1_1") (pintype "passive"))
      (node (ref "R14") (pin "1") (pinfunction "1_1") (pintype "passive"))
      (node (ref "R16") (pin "1") (pinfunction "1_1") (pintype "passive"))
      (node (ref "R18") (pin "1") (pinfunction "1_1") (pintype "passive"))
      (node (ref "R20") (pin "1") (pinfunction "1_1") (pintype "passive"))
      (node (ref "R22") (pin "1") (pinfunction "1_1") (pintype "passive"))
      (node (ref "R24") (pin "1") (pinfunction "1_1") (pintype "passive"))
      (node (ref "R26") (pin "1") (pinfunction "1_1") (pintype "passive"))
      (node (ref "R42") (pin "1") (pinfunction "1_1") (pintype "passive"))
      (node (ref "T8") (pin "1") (pinfunction "C_1") (pintype "passive"))
      (node (ref "U12") (pin "1") (pinfunction "1_1") (pintype "passive"))
    )
    (net (code "16") (name "Net-(C1-Pad1)") (class "Default")
      (node (ref "C1") (pin "1") (pinfunction "1_1") (pintype "passive"))
      (node (ref "R4") (pin "1") (pinfunction "1_1") (pintype "passive"))
      (node (ref "T1") (pin "B") (pinfunction "B_B") (pintype "passive"))
    )
    (net (code "17") (name "Net-(C2-Pad1)") (class "Default")
      (node (ref "C2") (pin "1") (pinfunction "1_1") (pintype "passive"))
      (node (ref "R5") (pin "1") (pinfunction "1_1") (pintype "passive"))
      (node (ref "T2") (pin "B") (pinfunction "B_B") (pintype "passive"))
    )
    (net (code "18") (name "Net-(C3-Pad1)") (class "Default")
      (node (ref "C3") (pin "1") (pinfunction "1_1") (pintype "passive"))
      (node (ref "R6") (pin "1") (pinfunction "1_1") (pintype "passive"))
      (node (ref "T3") (pin "B") (pinfunction "B_B") (pintype "passive"))
    )
    (net (code "19") (name "Net-(C4-Pad1)") (class "Default")
      (node (ref "C4") (pin "1") (pinfunction "1_1") (pintype "passive"))
      (node (ref "R7") (pin "1") (pinfunction "1_1") (pintype "passive"))
      (node (ref "T4") (pin "B") (pinfunction "B_B") (pintype "passive"))
    )
    (net (code "20") (name "Net-(C5-Pad1)") (class "Default")
      (node (ref "C5") (pin "1") (pinfunction "1_1") (pintype "passive"))
      (node (ref "R8") (pin "1") (pinfunction "1_1") (pintype "passive"))
      (node (ref "T5") (pin "B") (pinfunction "B_B") (pintype "passive"))
    )
    (net (code "21") (name "Net-(C6-Pad1)") (class "Default")
      (node (ref "C6") (pin "1") (pinfunction "1_1") (pintype "passive"))
      (node (ref "R9") (pin "1") (pinfunction "1_1") (pintype "passive"))
      (node (ref "T6") (pin "B") (pinfunction "B_B") (pintype "passive"))
    )
    (net (code "22") (name "Net-(C7-Pad1)") (class "Default")
      (node (ref "C7") (pin "1") (pinfunction "1_1") (pintype "passive"))
      (node (ref "R10") (pin "1") (pinfunction "1_1") (pintype "passive"))
      (node (ref "T7") (pin "B") (pinfunction "B_B") (pintype "passive"))
    )
    (net (code "23") (name "Net-(C61-Pad2)") (class "Default")
      (node (ref "C61") (pin "2") (pinfunction "2_2") (pintype "passive"))
      (node (ref "R38") (pin "2") (pinfunction "2_2") (pintype "passive"))
    )
    (net (code "24") (name "Net-(IC1-A0)") (class "Default")
      (node (ref "IC1") (pin "4") (pinfunction "A1_4") (pintype "bidirectional"))
      (node (ref "IC1") (pin "5") (pinfunction "A0_5") (pintype "bidirectional"))
    )
    (net (code "25") (name "Net-(IC1-GND-Pad11)") (class "Default")
      (node (ref "IC1") (pin "11") (pinfunction "GND_11") (pintype "bidirectional"))
      (node (ref "IC1") (pin "6") (pinfunction "GND_6") (pintype "bidirectional"))
    )
    (net (code "26") (name "Net-(J1-PWR_OK)") (class "Default")
      (node (ref "J1") (pin "8") (pinfunction "PWR_OK_8") (pintype "bidirectional"))
      (node (ref "LED1") (pin "A") (pinfunction "A_A") (pintype "passive"))
    )
    (net (code "27") (name "Net-(LED1-C)") (class "Default")
      (node (ref "LED1") (pin "K") (pinfunction "C_K") (pintype "passive"))
      (node (ref "R1") (pin "2") (pinfunction "2_2") (pintype "passive"))
    )
    (net (code "28") (name "Net-(Q1-PadB)") (class "Default")
      (node (ref "Q1") (pin "B") (pinfunction "B_B") (pintype "passive"))
      (node (ref "T1") (pin "C") (pinfunction "C_C") (pintype "passive"))
    )
    (net (code "29") (name "Net-(Q2-PadB)") (class "Default")
      (node (ref "Q2") (pin "B") (pinfunction "B_B") (pintype "passive"))
      (node (ref "T2") (pin "C") (pinfunction "C_C") (pintype "passive"))
    )
    (net (code "30") (name "Net-(Q3-PadB)") (class "Default")
      (node (ref "Q3") (pin "B") (pinfunction "B_B") (pintype "passive"))
      (node (ref "T3") (pin "C") (pinfunction "C_C") (pintype "passive"))
    )
    (net (code "31") (name "Net-(Q4-PadB)") (class "Default")
      (node (ref "Q4") (pin "B") (pinfunction "B_B") (pintype "passive"))
      (node (ref "T4") (pin "C") (pinfunction "C_C") (pintype "passive"))
    )
    (net (code "32") (name "Net-(Q5-PadB)") (class "Default")
      (node (ref "Q5") (pin "B") (pinfunction "B_B") (pintype "passive"))
      (node (ref "T5") (pin "C") (pinfunction "C_C") (pintype "passive"))
    )
    (net (code "33") (name "Net-(Q6-PadB)") (class "Default")
      (node (ref "Q6") (pin "B") (pinfunction "B_B") (pintype "passive"))
      (node (ref "T6") (pin "C") (pinfunction "C_C") (pintype "passive"))
    )
    (net (code "34") (name "Net-(Q7-PadB)") (class "Default")
      (node (ref "Q7") (pin "B") (pinfunction "B_B") (pintype "passive"))
      (node (ref "T7") (pin "C") (pinfunction "C_C") (pintype "passive"))
    )
    (net (code "35") (name "Net-(Q8-B)") (class "Default")
      (node (ref "Q8") (pin "2") (pinfunction "B_2") (pintype "passive"))
      (node (ref "R40") (pin "1") (pinfunction "1_1") (pintype "passive"))
      (node (ref "R42") (pin "2") (pinfunction "2_2") (pintype "passive"))
    )
    (net (code "36") (name "Net-(Q8-C)") (class "Default")
      (node (ref "Q8") (pin "1") (pinfunction "C_1") (pintype "passive"))
      (node (ref "R41") (pin "2") (pinfunction "2_2") (pintype "passive"))
      (node (ref "U15") (pin "3") (pinfunction "VFB_3") (pintype "passive"))
    )
    (net (code "37") (name "Net-(Q8-E)") (class "Default")
      (node (ref "C64") (pin "1") (pinfunction "1_1") (pintype "passive"))
      (node (ref "Q8") (pin "3") (pinfunction "E_3") (pintype "passive"))
      (node (ref "R39") (pin "1") (pinfunction "1_1") (pintype "passive"))
    )
    (net (code "38") (name "Net-(R27-A)") (class "Default")
      (node (ref "R27") (pin "1") (pinfunction "A_1") (pintype "passive"))
      (node (ref "R31") (pin "2") (pinfunction "2_2") (pintype "passive"))
      (node (ref "R32") (pin "2") (pinfunction "2_2") (pintype "passive"))
      (node (ref "R33") (pin "2") (pinfunction "2_2") (pintype "passive"))
      (node (ref "U10") (pin "7") (pinfunction "SET_7") (pintype "passive"))
      (node (ref "U12") (pin "2") (pinfunction "2_2") (pintype "passive"))
      (node (ref "U3") (pin "7") (pinfunction "SET_7") (pintype "passive"))
      (node (ref "U4") (pin "7") (pinfunction "SET_7") (pintype "passive"))
      (node (ref "U5") (pin "7") (pinfunction "SET_7") (pintype "passive"))
      (node (ref "U6") (pin "7") (pinfunction "SET_7") (pintype "passive"))
      (node (ref "U7") (pin "7") (pinfunction "SET_7") (pintype "passive"))
      (node (ref "U8") (pin "7") (pinfunction "SET_7") (pintype "passive"))
      (node (ref "U9") (pin "7") (pinfunction "SET_7") (pintype "passive"))
    )
    (net (code "39") (name "Net-(R28-A)") (class "Default")
      (node (ref "R28") (pin "1") (pinfunction "A_1") (pintype "passive"))
      (node (ref "R29") (pin "1") (pinfunction "1_1") (pintype "passive"))
      (node (ref "R30") (pin "1") (pinfunction "1_1") (pintype "passive"))
    )
    (net (code "40") (name "Net-(R28-E)") (class "Default")
      (node (ref "C12") (pin "2") (pinfunction "2_2") (pintype "passive"))
      (node (ref "C13") (pin "2") (pinfunction "2_2") (pintype "passive"))
      (node (ref "C14") (pin "2") (pinfunction "2_2") (pintype "passive"))
      (node (ref "R11") (pin "2") (pinfunction "2_2") (pintype "passive"))
      (node (ref "R12") (pin "2") (pinfunction "2_2") (pintype "passive"))
      (node (ref "R28") (pin "3") (pinfunction "E_3") (pintype "passive"))
      (node (ref "R29") (pin "2") (pinfunction "2_2") (pintype "passive"))
      (node (ref "U3") (pin "1") (pinfunction "OUT_2_1") (pintype "output"))
      (node (ref "U3") (pin "10") (pinfunction "IMON_10") (pintype "passive"))
      (node (ref "U3") (pin "11") (pinfunction "TEMP_11") (pintype "passive"))
      (node (ref "U3") (pin "16") (pinfunction "OUT_9_16") (pintype "output"))
      (node (ref "U3") (pin "17") (pinfunction "OUT_17") (pintype "output"))
      (node (ref "U3") (pin "2") (pinfunction "OUT_3_2") (pintype "output"))
      (node (ref "U3") (pin "3") (pinfunction "OUT_4_3") (pintype "output"))
      (node (ref "U3") (pin "4") (pinfunction "OUT_5_4") (pintype "output"))
      (node (ref "U3") (pin "5") (pinfunction "OUT_6_5") (pintype "output"))
      (node (ref "U3") (pin "8") (pinfunction "OUT_7_8") (pintype "output"))
      (node (ref "U3") (pin "9") (pinfunction "OUT_8_9") (pintype "output"))
    )
    (net (code "41") (name "Net-(SJ5-Pad2)") (class "Default")
      (node (ref "SJ5") (pin "2") (pinfunction "2_2") (pintype "passive"))
      (node (ref "SJ6") (pin "2") (pinfunction "2_2") (pintype "passive"))
    )
    (net (code "42") (name "Net-(T8-E)") (class "Default")
      (node (ref "R36") (pin "1") (pinfunction "1_1") (pintype "passive"))
      (node (ref "T8") (pin "3") (pinfunction "E_3") (pintype "passive"))
    )
    (net (code "43") (name "Net-(U1-CAP+)") (class "Default")
      (node (ref "C8") (pin "1") (pinfunction "1_1") (pintype "passive"))
      (node (ref "U1") (pin "2") (pinfunction "CAP+_2") (pintype "passive"))
    )
    (net (code "44") (name "Net-(U1-CAP-)") (class "Default")
      (node (ref "C8") (pin "2") (pinfunction "2_2") (pintype "passive"))
      (node (ref "U1") (pin "4") (pinfunction "CAP-_4") (pintype "passive"))
    )
    (net (code "45") (name "Net-(U2-CAP+)") (class "Default")
      (node (ref "C10") (pin "1") (pinfunction "1_1") (pintype "passive"))
      (node (ref "U2") (pin "2") (pinfunction "CAP+_2") (pintype "passive"))
    )
    (net (code "46") (name "Net-(U2-CAP-)") (class "Default")
      (node (ref "C10") (pin "2") (pinfunction "2_2") (pintype "passive"))
      (node (ref "U2") (pin "4") (pinfunction "CAP-_4") (pintype "passive"))
    )
    (net (code "47") (name "Net-(U4-IMON)") (class "Default")
      (node (ref "C17") (pin "2") (pinfunction "2_2") (pintype "passive"))
      (node (ref "C18") (pin "2") (pinfunction "2_2") (pintype "passive"))
      (node (ref "C19") (pin "2") (pinfunction "2_2") (pintype "passive"))
      (node (ref "R13") (pin "2") (pinfunction "2_2") (pintype "passive"))
      (node (ref "R14") (pin "2") (pinfunction "2_2") (pintype "passive"))
      (node (ref "U4") (pin "1") (pinfunction "OUT_2_1") (pintype "output"))
      (node (ref "U4") (pin "10") (pinfunction "IMON_10") (pintype "passive"))
      (node (ref "U4") (pin "11") (pinfunction "TEMP_11") (pintype "passive"))
      (node (ref "U4") (pin "16") (pinfunction "OUT_9_16") (pintype "output"))
      (node (ref "U4") (pin "17") (pinfunction "OUT_17") (pintype "output"))
      (node (ref "U4") (pin "2") (pinfunction "OUT_3_2") (pintype "output"))
      (node (ref "U4") (pin "3") (pinfunction "OUT_4_3") (pintype "output"))
      (node (ref "U4") (pin "4") (pinfunction "OUT_5_4") (pintype "output"))
      (node (ref "U4") (pin "5") (pinfunction "OUT_6_5") (pintype "output"))
      (node (ref "U4") (pin "8") (pinfunction "OUT_7_8") (pintype "output"))
      (node (ref "U4") (pin "9") (pinfunction "OUT_8_9") (pintype "output"))
    )
    (net (code "48") (name "Net-(U5-IMON)") (class "Default")
      (node (ref "C22") (pin "2") (pinfunction "2_2") (pintype "passive"))
      (node (ref "C23") (pin "2") (pinfunction "2_2") (pintype "passive"))
      (node (ref "C24") (pin "2") (pinfunction "2_2") (pintype "passive"))
      (node (ref "R15") (pin "2") (pinfunction "2_2") (pintype "passive"))
      (node (ref "R16") (pin "2") (pinfunction "2_2") (pintype "passive"))
      (node (ref "U5") (pin "1") (pinfunction "OUT_2_1") (pintype "output"))
      (node (ref "U5") (pin "10") (pinfunction "IMON_10") (pintype "passive"))
      (node (ref "U5") (pin "11") (pinfunction "TEMP_11") (pintype "passive"))
      (node (ref "U5") (pin "16") (pinfunction "OUT_9_16") (pintype "output"))
      (node (ref "U5") (pin "17") (pinfunction "OUT_17") (pintype "output"))
      (node (ref "U5") (pin "2") (pinfunction "OUT_3_2") (pintype "output"))
      (node (ref "U5") (pin "3") (pinfunction "OUT_4_3") (pintype "output"))
      (node (ref "U5") (pin "4") (pinfunction "OUT_5_4") (pintype "output"))
      (node (ref "U5") (pin "5") (pinfunction "OUT_6_5") (pintype "output"))
      (node (ref "U5") (pin "8") (pinfunction "OUT_7_8") (pintype "output"))
      (node (ref "U5") (pin "9") (pinfunction "OUT_8_9") (pintype "output"))
    )
    (net (code "49") (name "Net-(U6-IMON)") (class "Default")
      (node (ref "C27") (pin "2") (pinfunction "2_2") (pintype "passive"))
      (node (ref "C28") (pin "2") (pinfunction "2_2") (pintype "passive"))
      (node (ref "C29") (pin "2") (pinfunction "2_2") (pintype "passive"))
      (node (ref "R17") (pin "2") (pinfunction "2_2") (pintype "passive"))
      (node (ref "R18") (pin "2") (pinfunction "2_2") (pintype "passive"))
      (node (ref "U6") (pin "1") (pinfunction "OUT_2_1") (pintype "output"))
      (node (ref "U6") (pin "10") (pinfunction "IMON_10") (pintype "passive"))
      (node (ref "U6") (pin "11") (pinfunction "TEMP_11") (pintype "passive"))
      (node (ref "U6") (pin "16") (pinfunction "OUT_9_16") (pintype "output"))
      (node (ref "U6") (pin "17") (pinfunction "OUT_17") (pintype "output"))
      (node (ref "U6") (pin "2") (pinfunction "OUT_3_2") (pintype "output"))
      (node (ref "U6") (pin "3") (pinfunction "OUT_4_3") (pintype "output"))
      (node (ref "U6") (pin "4") (pinfunction "OUT_5_4") (pintype "output"))
      (node (ref "U6") (pin "5") (pinfunction "OUT_6_5") (pintype "output"))
      (node (ref "U6") (pin "8") (pinfunction "OUT_7_8") (pintype "output"))
      (node (ref "U6") (pin "9") (pinfunction "OUT_8_9") (pintype "output"))
    )
    (net (code "50") (name "Net-(U7-IMON)") (class "Default")
      (node (ref "C32") (pin "2") (pinfunction "2_2") (pintype "passive"))
      (node (ref "C33") (pin "2") (pinfunction "2_2") (pintype "passive"))
      (node (ref "C34") (pin "2") (pinfunction "2_2") (pintype "passive"))
      (node (ref "R19") (pin "2") (pinfunction "2_2") (pintype "passive"))
      (node (ref "R20") (pin "2") (pinfunction "2_2") (pintype "passive"))
      (node (ref "U7") (pin "1") (pinfunction "OUT_2_1") (pintype "output"))
      (node (ref "U7") (pin "10") (pinfunction "IMON_10") (pintype "passive"))
      (node (ref "U7") (pin "11") (pinfunction "TEMP_11") (pintype "passive"))
      (node (ref "U7") (pin "16") (pinfunction "OUT_9_16") (pintype "output"))
      (node (ref "U7") (pin "17") (pinfunction "OUT_17") (pintype "output"))
      (node (ref "U7") (pin "2") (pinfunction "OUT_3_2") (pintype "output"))
      (node (ref "U7") (pin "3") (pinfunction "OUT_4_3") (pintype "output"))
      (node (ref "U7") (pin "4") (pinfunction "OUT_5_4") (pintype "output"))
      (node (ref "U7") (pin "5") (pinfunction "OUT_6_5") (pintype "output"))
      (node (ref "U7") (pin "8") (pinfunction "OUT_7_8") (pintype "output"))
      (node (ref "U7") (pin "9") (pinfunction "OUT_8_9") (pintype "output"))
    )
    (net (code "51") (name "Net-(U8-IMON)") (class "Default")
      (node (ref "C37") (pin "2") (pinfunction "2_2") (pintype "passive"))
      (node (ref "C38") (pin "2") (pinfunction "2_2") (pintype "passive"))
      (node (ref "C39") (pin "2") (pinfunction "2_2") (pintype "passive"))
      (node (ref "R21") (pin "2") (pinfunction "2_2") (pintype "passive"))
      (node (ref "R22") (pin "2") (pinfunction "2_2") (pintype "passive"))
      (node (ref "U8") (pin "1") (pinfunction "OUT_2_1") (pintype "output"))
      (node (ref "U8") (pin "10") (pinfunction "IMON_10") (pintype "passive"))
      (node (ref "U8") (pin "11") (pinfunction "TEMP_11") (pintype "passive"))
      (node (ref "U8") (pin "16") (pinfunction "OUT_9_16") (pintype "output"))
      (node (ref "U8") (pin "17") (pinfunction "OUT_17") (pintype "output"))
      (node (ref "U8") (pin "2") (pinfunction "OUT_3_2") (pintype "output"))
      (node (ref "U8") (pin "3") (pinfunction "OUT_4_3") (pintype "output"))
      (node (ref "U8") (pin "4") (pinfunction "OUT_5_4") (pintype "output"))
      (node (ref "U8") (pin "5") (pinfunction "OUT_6_5") (pintype "output"))
      (node (ref "U8") (pin "8") (pinfunction "OUT_7_8") (pintype "output"))
      (node (ref "U8") (pin "9") (pinfunction "OUT_8_9") (pintype "output"))
    )
    (net (code "52") (name "Net-(U9-IMON)") (class "Default")
      (node (ref "C42") (pin "2") (pinfunction "2_2") (pintype "passive"))
      (node (ref "C43") (pin "2") (pinfunction "2_2") (pintype "passive"))
      (node (ref "C44") (pin "2") (pinfunction "2_2") (pintype "passive"))
      (node (ref "R23") (pin "2") (pinfunction "2_2") (pintype "passive"))
      (node (ref "R24") (pin "2") (pinfunction "2_2") (pintype "passive"))
      (node (ref "U9") (pin "1") (pinfunction "OUT_2_1") (pintype "output"))
      (node (ref "U9") (pin "10") (pinfunction "IMON_10") (pintype "passive"))
      (node (ref "U9") (pin "11") (pinfunction "TEMP_11") (pintype "passive"))
      (node (ref "U9") (pin "16") (pinfunction "OUT_9_16") (pintype "output"))
      (node (ref "U9") (pin "17") (pinfunction "OUT_17") (pintype "output"))
      (node (ref "U9") (pin "2") (pinfunction "OUT_3_2") (pintype "output"))
      (node (ref "U9") (pin "3") (pinfunction "OUT_4_3") (pintype "output"))
      (node (ref "U9") (pin "4") (pinfunction "OUT_5_4") (pintype "output"))
      (node (ref "U9") (pin "5") (pinfunction "OUT_6_5") (pintype "output"))
      (node (ref "U9") (pin "8") (pinfunction "OUT_7_8") (pintype "output"))
      (node (ref "U9") (pin "9") (pinfunction "OUT_8_9") (pintype "output"))
    )
    (net (code "53") (name "Net-(U10-ILIM)") (class "Default")
      (node (ref "R30") (pin "2") (pinfunction "2_2") (pintype "passive"))
      (node (ref "U10") (pin "6") (pinfunction "ILIM_6") (pintype "passive"))
      (node (ref "U3") (pin "6") (pinfunction "ILIM_6") (pintype "passive"))
      (node (ref "U4") (pin "6") (pinfunction "ILIM_6") (pintype "passive"))
      (node (ref "U5") (pin "6") (pinfunction "ILIM_6") (pintype "passive"))
      (node (ref "U6") (pin "6") (pinfunction "ILIM_6") (pintype "passive"))
      (node (ref "U7") (pin "6") (pinfunction "ILIM_6") (pintype "passive"))
      (node (ref "U8") (pin "6") (pinfunction "ILIM_6") (pintype "passive"))
      (node (ref "U9") (pin "6") (pinfunction "ILIM_6") (pintype "passive"))
    )
    (net (code "54") (name "Net-(U10-IMON)") (class "Default")
      (node (ref "C47") (pin "2") (pinfunction "2_2") (pintype "passive"))
      (node (ref "C48") (pin "2") (pinfunction "2_2") (pintype "passive"))
      (node (ref "C49") (pin "2") (pinfunction "2_2") (pintype "passive"))
      (node (ref "R25") (pin "2") (pinfunction "2_2") (pintype "passive"))
      (node (ref "R26") (pin "2") (pinfunction "2_2") (pintype "passive"))
      (node (ref "U10") (pin "1") (pinfunction "OUT_2_1") (pintype "output"))
      (node (ref "U10") (pin "10") (pinfunction "IMON_10") (pintype "passive"))
      (node (ref "U10") (pin "11") (pinfunction "TEMP_11") (pintype "passive"))
      (node (ref "U10") (pin "16") (pinfunction "OUT_9_16") (pintype "output"))
      (node (ref "U10") (pin "17") (pinfunction "OUT_17") (pintype "output"))
      (node (ref "U10") (pin "2") (pinfunction "OUT_3_2") (pintype "output"))
      (node (ref "U10") (pin "3") (pinfunction "OUT_4_3") (pintype "output"))
      (node (ref "U10") (pin "4") (pinfunction "OUT_5_4") (pintype "output"))
      (node (ref "U10") (pin "5") (pinfunction "OUT_6_5") (pintype "output"))
      (node (ref "U10") (pin "8") (pinfunction "OUT_7_8") (pintype "output"))
      (node (ref "U10") (pin "9") (pinfunction "OUT_8_9") (pintype "output"))
    )
    (net (code "55") (name "Net-(U11-EP)") (class "Default")
      (node (ref "R31") (pin "1") (pinfunction "1_1") (pintype "passive"))
      (node (ref "U11") (pin "1") (pinfunction "OUT_2_1") (pintype "output"))
      (node (ref "U11") (pin "2") (pinfunction "OUT_2") (pintype "output"))
      (node (ref "U11") (pin "9") (pinfunction "EP_9") (pintype "passive"))
    )
    (net (code "56") (name "Net-(U11-SET)") (class "Default")
      (node (ref "R32") (pin "1") (pinfunction "1_1") (pintype "passive"))
      (node (ref "R33") (pin "1") (pinfunction "1_1") (pintype "passive"))
      (node (ref "U11") (pin "4") (pinfunction "SET_4") (pintype "input"))
    )
    (net (code "57") (name "Net-(U14-C+)") (class "Default")
      (node (ref "C57") (pin "2") (pinfunction "2_2") (pintype "passive"))
      (node (ref "U14") (pin "3") (pinfunction "C+_3") (pintype "passive"))
    )
    (net (code "58") (name "Net-(U14-C-)") (class "Default")
      (node (ref "C57") (pin "1") (pinfunction "1_1") (pintype "passive"))
      (node (ref "U14") (pin "4") (pinfunction "C-_4") (pintype "passive"))
    )
    (net (code "59") (name "Net-(U14-VOUT)") (class "Default")
      (node (ref "C58") (pin "1") (pinfunction "1_1") (pintype "passive"))
      (node (ref "R36") (pin "2") (pinfunction "2_2") (pintype "passive"))
      (node (ref "U14") (pin "2") (pinfunction "VOUT_2") (pintype "output"))
    )
    (net (code "60") (name "Net-(U15-BOOST)") (class "Default")
      (node (ref "C62") (pin "2") (pinfunction "2_2") (pintype "passive"))
      (node (ref "U15") (pin "7") (pinfunction "BOOST_7") (pintype "power_in"))
    )
    (net (code "61") (name "Net-(U15-ITH{slash}RUN)") (class "Default")
      (node (ref "C61") (pin "1") (pinfunction "1_1") (pintype "passive"))
      (node (ref "U15") (pin "2") (pinfunction "ITH/RUN_2") (pintype "passive"))
    )
    (net (code "62") (name "Net-(U15-SENSE-)") (class "Default")
      (node (ref "R37") (pin "1") (pinfunction "1_1") (pintype "passive"))
      (node (ref "U15") (pin "1") (pinfunction "SENSE-_1") (pintype "passive"))
      (node (ref "U16") (pin "2") (pinfunction "D_2") (pintype "passive"))
    )
    (net (code "63") (name "Net-(U15-SW)") (class "Default")
      (node (ref "C62") (pin "1") (pinfunction "1_1") (pintype "passive"))
      (node (ref "U$1") (pin "1") (pinfunction "1_1") (pintype "passive"))
      (node (ref "U15") (pin "5") (pinfunction "SW_5") (pintype "passive"))
      (node (ref "U16") (pin "3") (pinfunction "S_3") (pintype "passive"))
      (node (ref "U17") (pin "1") (pinfunction "1_1") (pintype "passive"))
    )
    (net (code "64") (name "Net-(U15-TG)") (class "Default")
      (node (ref "U15") (pin "6") (pinfunction "TG_6") (pintype "passive"))
      (node (ref "U16") (pin "1") (pinfunction "G_1") (pintype "passive"))
    )
    (net (code "65") (name "PSU_-3.3V_OUT") (class "Default")
      (node (ref "J16") (pin "P$1") (pinfunction "1_P$1") (pintype "passive"))
      (node (ref "Q6") (pin "C") (pinfunction "C_C") (pintype "passive"))
      (node (ref "SJ7") (pin "2") (pinfunction "2_2") (pintype "passive"))
      (node (ref "T6") (pin "E") (pinfunction "E_E") (pintype "passive"))
    )
    (net (code "66") (name "PSU_-5V") (class "Default")
      (node (ref "J1") (pin "20") (pinfunction "NC_20") (pintype "bidirectional"))
      (node (ref "SJ6") (pin "3") (pinfunction "3_3") (pintype "passive"))
    )
    (net (code "67") (name "PSU_-5V_OUT") (class "Default")
      (node (ref "J13") (pin "P$1") (pinfunction "1_P$1") (pintype "passive"))
      (node (ref "Q5") (pin "C") (pinfunction "C_C") (pintype "passive"))
      (node (ref "SJ5") (pin "3") (pinfunction "3_3") (pintype "passive"))
      (node (ref "T5") (pin "E") (pinfunction "E_E") (pintype "passive"))
    )
    (net (code "68") (name "PSU_-12V") (class "Default")
      (node (ref "J1") (pin "14") (pinfunction "-12V_14") (pintype "bidirectional"))
      (node (ref "SJ4") (pin "2") (pinfunction "2_2") (pintype "passive"))
    )
    (net (code "69") (name "PSU_-12V_OUT") (class "Default")
      (node (ref "J10") (pin "P$1") (pinfunction "1_P$1") (pintype "passive"))
      (node (ref "Q4") (pin "C") (pinfunction "C_C") (pintype "passive"))
      (node (ref "SJ4") (pin "3") (pinfunction "3_3") (pintype "passive"))
      (node (ref "T4") (pin "E") (pinfunction "E_E") (pintype "passive"))
    )
    (net (code "70") (name "PSU_3.3V") (class "Default")
      (node (ref "J1") (pin "1") (pinfunction "3.3V_1") (pintype "bidirectional"))
      (node (ref "J1") (pin "12") (pinfunction "3.3V_12") (pintype "bidirectional"))
      (node (ref "J1") (pin "13") (pinfunction "3.3V_13") (pintype "bidirectional"))
      (node (ref "J1") (pin "2") (pinfunction "3.3V_2") (pintype "bidirectional"))
      (node (ref "SJ2") (pin "2") (pinfunction "2_2") (pintype "passive"))
      (node (ref "U1") (pin "8") (pinfunction "VCC_8") (pintype "power_in"))
    )
    (net (code "71") (name "PSU_3.3V_OUT") (class "Default")
      (node (ref "J14") (pin "P$1") (pinfunction "1_P$1") (pintype "passive"))
      (node (ref "Q3") (pin "C") (pinfunction "C_C") (pintype "passive"))
      (node (ref "SJ2") (pin "3") (pinfunction "3_3") (pintype "passive"))
      (node (ref "T3") (pin "E") (pinfunction "E_E") (pintype "passive"))
    )
    (net (code "72") (name "PSU_5V") (class "Default")
      (node (ref "J1") (pin "21") (pinfunction "5V_21") (pintype "bidirectional"))
      (node (ref "J1") (pin "22") (pinfunction "5V_22") (pintype "bidirectional"))
      (node (ref "J1") (pin "23") (pinfunction "5V_23") (pintype "bidirectional"))
      (node (ref "J1") (pin "4") (pinfunction "5V_4") (pintype "bidirectional"))
      (node (ref "J1") (pin "6") (pinfunction "5V_6") (pintype "bidirectional"))
      (node (ref "R2") (pin "1") (pinfunction "1_1") (pintype "passive"))
      (node (ref "SJ1") (pin "2") (pinfunction "2_2") (pintype "passive"))
      (node (ref "U2") (pin "8") (pinfunction "VCC_8") (pintype "power_in"))
    )
    (net (code "73") (name "PSU_5V_OUT") (class "Default")
      (node (ref "J11") (pin "P$1") (pinfunction "1_P$1") (pintype "passive"))
      (node (ref "Q2") (pin "C") (pinfunction "C_C") (pintype "passive"))
      (node (ref "SJ1") (pin "3") (pinfunction "3_3") (pintype "passive"))
      (node (ref "T2") (pin "E") (pinfunction "E_E") (pintype "passive"))
    )
    (net (code "74") (name "PSU_12V") (class "Default")
      (node (ref "J1") (pin "10") (pinfunction "12V_10") (pintype "bidirectional"))
      (node (ref "J1") (pin "11") (pinfunction "12V_11") (pintype "bidirectional"))
      (node (ref "R3") (pin "1") (pinfunction "1_1") (pintype "passive"))
      (node (ref "SJ3") (pin "2") (pinfunction "2_2") (pintype "passive"))
    )
    (net (code "75") (name "PSU_12V_OUT") (class "Default")
      (node (ref "J8") (pin "P$1") (pinfunction "1_P$1") (pintype "passive"))
      (node (ref "Q1") (pin "C") (pinfunction "C_C") (pintype "passive"))
      (node (ref "SJ3") (pin "3") (pinfunction "3_3") (pintype "passive"))
      (node (ref "T1") (pin "E") (pinfunction "E_E") (pintype "passive"))
    )
    (net (code "76") (name "PSU_GND") (class "Default")
      (node (ref "C1") (pin "2") (pinfunction "2_2") (pintype "passive"))
      (node (ref "C11") (pin "2") (pinfunction "2_2") (pintype "passive"))
      (node (ref "C2") (pin "2") (pinfunction "2_2") (pintype "passive"))
      (node (ref "C3") (pin "2") (pinfunction "2_2") (pintype "passive"))
      (node (ref "C4") (pin "2") (pinfunction "2_2") (pintype "passive"))
      (node (ref "C5") (pin "2") (pinfunction "2_2") (pintype "passive"))
      (node (ref "C6") (pin "2") (pinfunction "2_2") (pintype "passive"))
      (node (ref "C9") (pin "2") (pinfunction "2_2") (pintype "passive"))
      (node (ref "J1") (pin "15") (pinfunction "GND_15") (pintype "bidirectional"))
      (node (ref "J1") (pin "16") (pinfunction "PS_ON_16") (pintype "bidirectional"))
      (node (ref "J1") (pin "17") (pinfunction "GND_17") (pintype "bidirectional"))
      (node (ref "J1") (pin "18") (pinfunction "GND_18") (pintype "bidirectional"))
      (node (ref "J1") (pin "19") (pinfunction "GND_19") (pintype "bidirectional"))
      (node (ref "J1") (pin "24") (pinfunction "GND_24") (pintype "bidirectional"))
      (node (ref "J1") (pin "3") (pinfunction "GND_3") (pintype "bidirectional"))
      (node (ref "J1") (pin "5") (pinfunction "GND_5") (pintype "bidirectional"))
      (node (ref "J1") (pin "7") (pinfunction "GND_7") (pintype "bidirectional"))
      (node (ref "J12") (pin "P$1") (pinfunction "1_P$1") (pintype "passive"))
      (node (ref "J15") (pin "P$1") (pinfunction "1_P$1") (pintype "passive"))
      (node (ref "J9") (pin "P$1") (pinfunction "1_P$1") (pintype "passive"))
      (node (ref "R1") (pin "1") (pinfunction "1_1") (pintype "passive"))
      (node (ref "R2") (pin "2") (pinfunction "2_2") (pintype "passive"))
      (node (ref "R3") (pin "2") (pinfunction "2_2") (pintype "passive"))
      (node (ref "U1") (pin "3") (pinfunction "GND_3") (pintype "power_in"))
      (node (ref "U1") (pin "6") (pinfunction "LV_6") (pintype "passive"))
      (node (ref "U2") (pin "3") (pinfunction "GND_3") (pintype "power_in"))
    )
    (net (code "77") (name "SCL") (class "Default")
      (node (ref "IC1") (pin "9") (pinfunction "SCL_9") (pintype "bidirectional"))
      (node (ref "R34") (pin "1") (pinfunction "1_1") (pintype "passive"))
    )
    (net (code "78") (name "SDA") (class "Default")
      (node (ref "IC1") (pin "8") (pinfunction "SDA_8") (pintype "bidirectional"))
      (node (ref "R35") (pin "1") (pinfunction "1_1") (pintype "passive"))
    )
    (net (code "79") (name "VIN") (class "Default")
      (node (ref "C54") (pin "2") (pinfunction "2_2") (pintype "passive"))
      (node (ref "C55") (pin "2") (pinfunction "2_2") (pintype "passive"))
      (node (ref "C59") (pin "2") (pinfunction "2_2") (pintype "passive"))
      (node (ref "C60") (pin "2") (pinfunction "2_2") (pintype "passive"))
      (node (ref "C63") (pin "2") (pinfunction "2_2") (pintype "passive"))
      (node (ref "C65") (pin "1") (pinfunction "1_1") (pintype "passive"))
      (node (ref "R37") (pin "2") (pinfunction "2_2") (pintype "passive"))
      (node (ref "U11") (pin "7") (pinfunction "IN_2_7") (pintype "input"))
      (node (ref "U11") (pin "8") (pinfunction "IN_8") (pintype "input"))
      (node (ref "U13") (pin "3") (pinfunction "EN_3") (pintype "input"))
      (node (ref "U13") (pin "5") (pinfunction "VCC_5") (pintype "input"))
      (node (ref "U15") (pin "8") (pinfunction "VIN_8") (pintype "power_in"))
    )
    (net (code "80") (name "V_ADJ_OUT") (class "Default")
      (node (ref "J17") (pin "P$1") (pinfunction "1_P$1") (pintype "passive"))
      (node (ref "Q7") (pin "C") (pinfunction "C_C") (pintype "passive"))
      (node (ref "T7") (pin "E") (pinfunction "E_E") (pintype "passive"))
    )
    (net (code "81") (name "V_ADJ_RIPPLE") (class "Default")
      (node (ref "Q7") (pin "E") (pinfunction "E_E") (pintype "passive"))
      (node (ref "R10") (pin "2") (pinfunction "2_2") (pintype "passive"))
    )
    (net (code "82") (name "unconnected-(IC1-ALERT-Pad7)") (class "Default")
      (node (ref "IC1") (pin "7") (pinfunction "ALERT_7") (pintype "bidirectional"))
    )
    (net (code "83") (name "unconnected-(IC1-NC-Pad13)") (class "Default")
      (node (ref "IC1") (pin "13") (pinfunction "NC_13") (pintype "bidirectional"))
    )
    (net (code "84") (name "unconnected-(J1-5V_STDBY-Pad9)") (class "Default")
      (node (ref "J1") (pin "9") (pinfunction "5V_STDBY_9") (pintype "bidirectional"))
    )
    (net (code "85") (name "unconnected-(R27-S-Pad2)") (class "Default")
      (node (ref "R27") (pin "2") (pinfunction "S_2") (pintype "passive"))
    )
    (net (code "86") (name "unconnected-(R28-S-Pad2)") (class "Default")
      (node (ref "R28") (pin "2") (pinfunction "S_2") (pintype "passive"))
    )
    (net (code "87") (name "unconnected-(U1-NC-Pad1)") (class "Default")
      (node (ref "U1") (pin "1") (pinfunction "NC_1") (pintype "passive"))
    )
    (net (code "88") (name "unconnected-(U1-OSC-Pad7)") (class "Default")
      (node (ref "U1") (pin "7") (pinfunction "OSC_7") (pintype "passive"))
    )
    (net (code "89") (name "unconnected-(U2-LV-Pad6)") (class "Default")
      (node (ref "U2") (pin "6") (pinfunction "LV_6") (pintype "passive"))
    )
    (net (code "90") (name "unconnected-(U2-NC-Pad1)") (class "Default")
      (node (ref "U2") (pin "1") (pinfunction "NC_1") (pintype "passive"))
    )
    (net (code "91") (name "unconnected-(U2-OSC-Pad7)") (class "Default")
      (node (ref "U2") (pin "7") (pinfunction "OSC_7") (pintype "passive"))
    )
    (net (code "92") (name "unconnected-(U11-NC-Pad3)") (class "Default")
      (node (ref "U11") (pin "3") (pinfunction "NC_3") (pintype "no_connect"))
    )
    (net (code "93") (name "unconnected-(U11-NC_2-Pad5)") (class "Default")
      (node (ref "U11") (pin "5") (pinfunction "NC_2_5") (pintype "no_connect"))
    )
    (net (code "94") (name "unconnected-(U11-NC_3-Pad6)") (class "Default")
      (node (ref "U11") (pin "6") (pinfunction "NC_3_6") (pintype "no_connect"))
    )
    (net (code "95") (name "unconnected-(U13-NC-Pad4)") (class "Default")
      (node (ref "U13") (pin "4") (pinfunction "NC_4") (pintype "input"))
    )
  )
)
